# watchplb_mainboard_v1_0.net
KiCad netlist of a schematic drawn in EAGLE
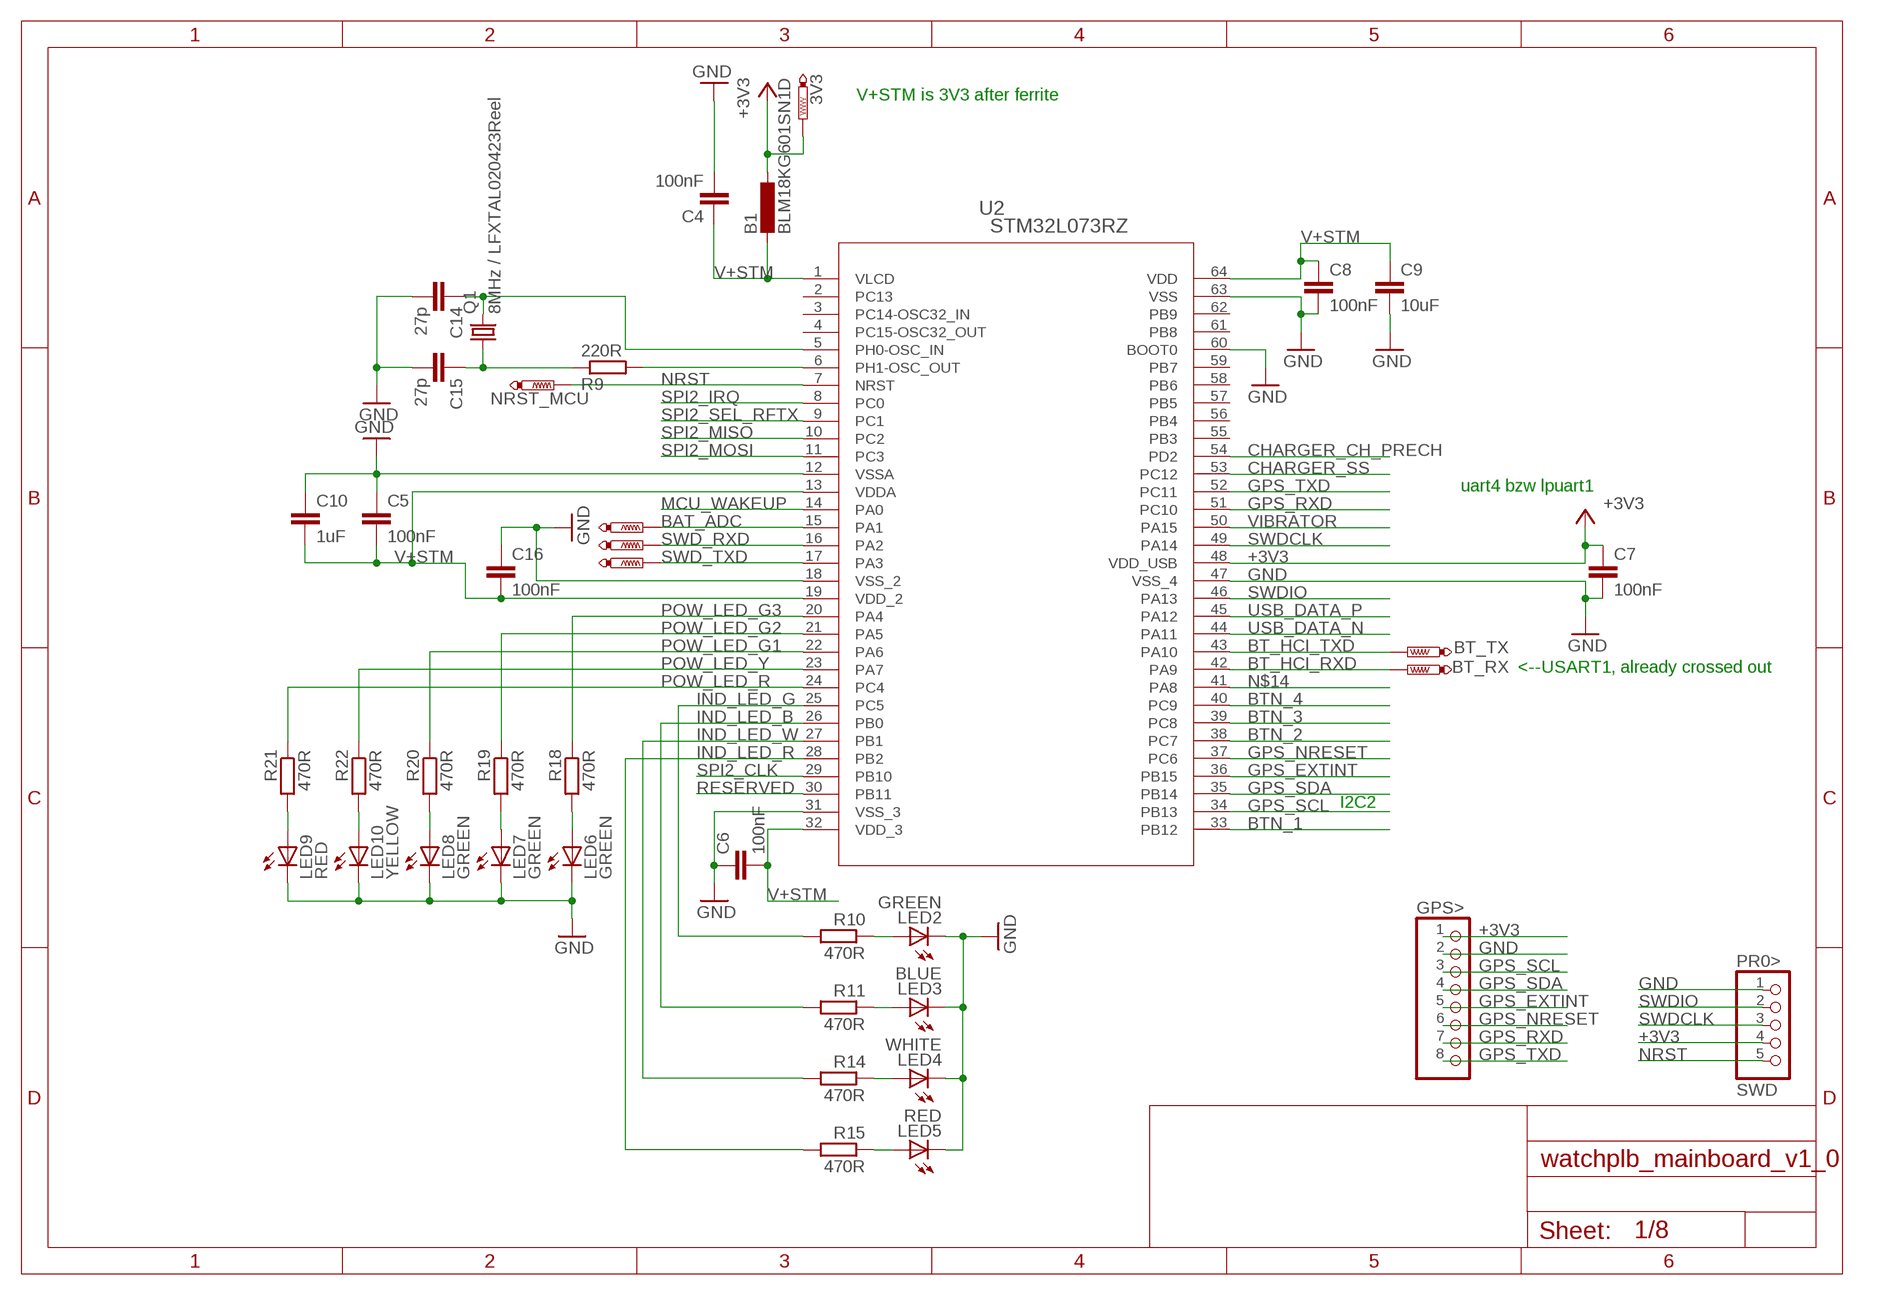
[diagram p0: schematic, sheet 1]
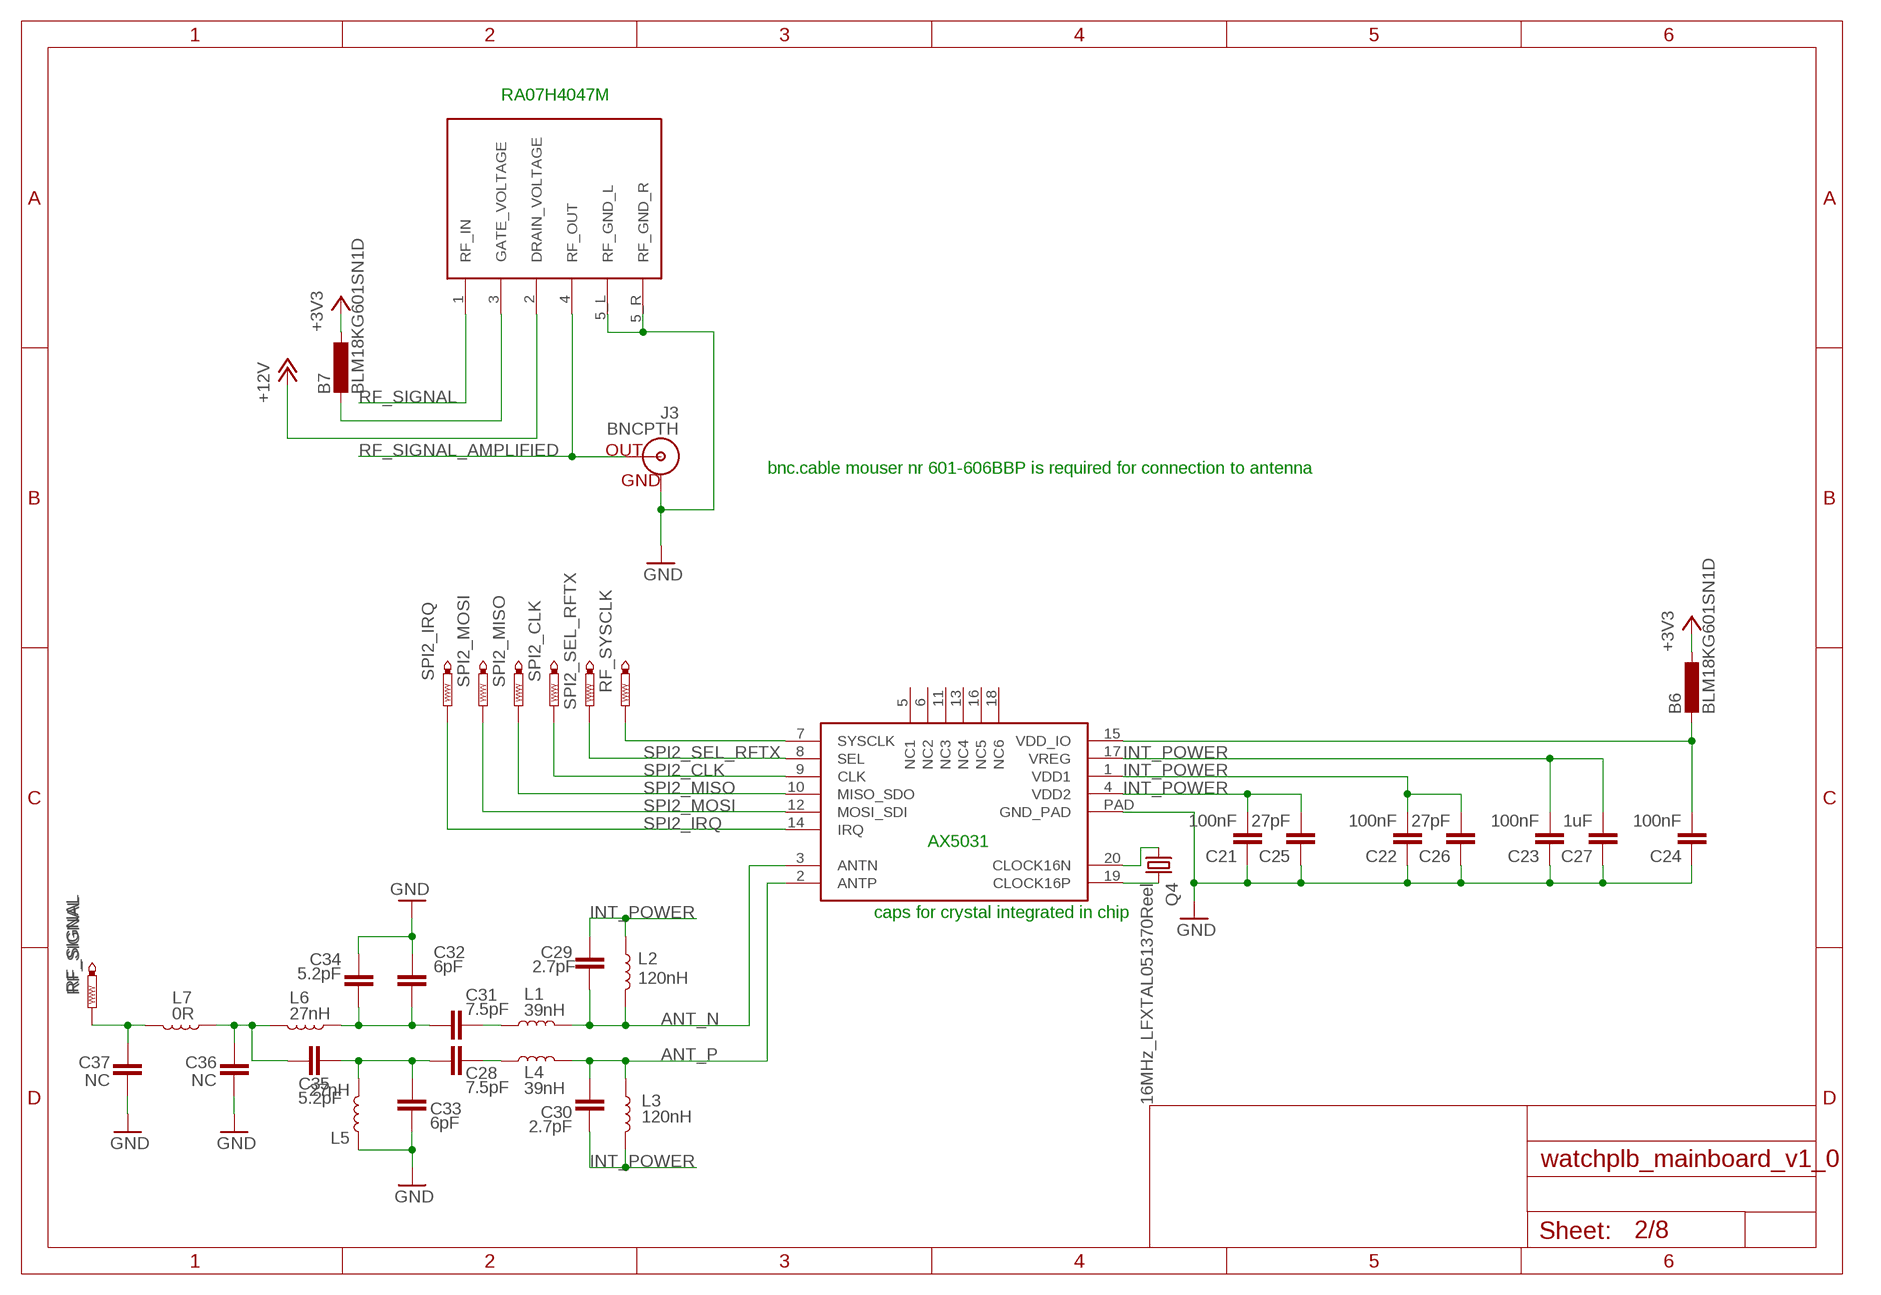
[diagram p1: schematic, sheet 2]
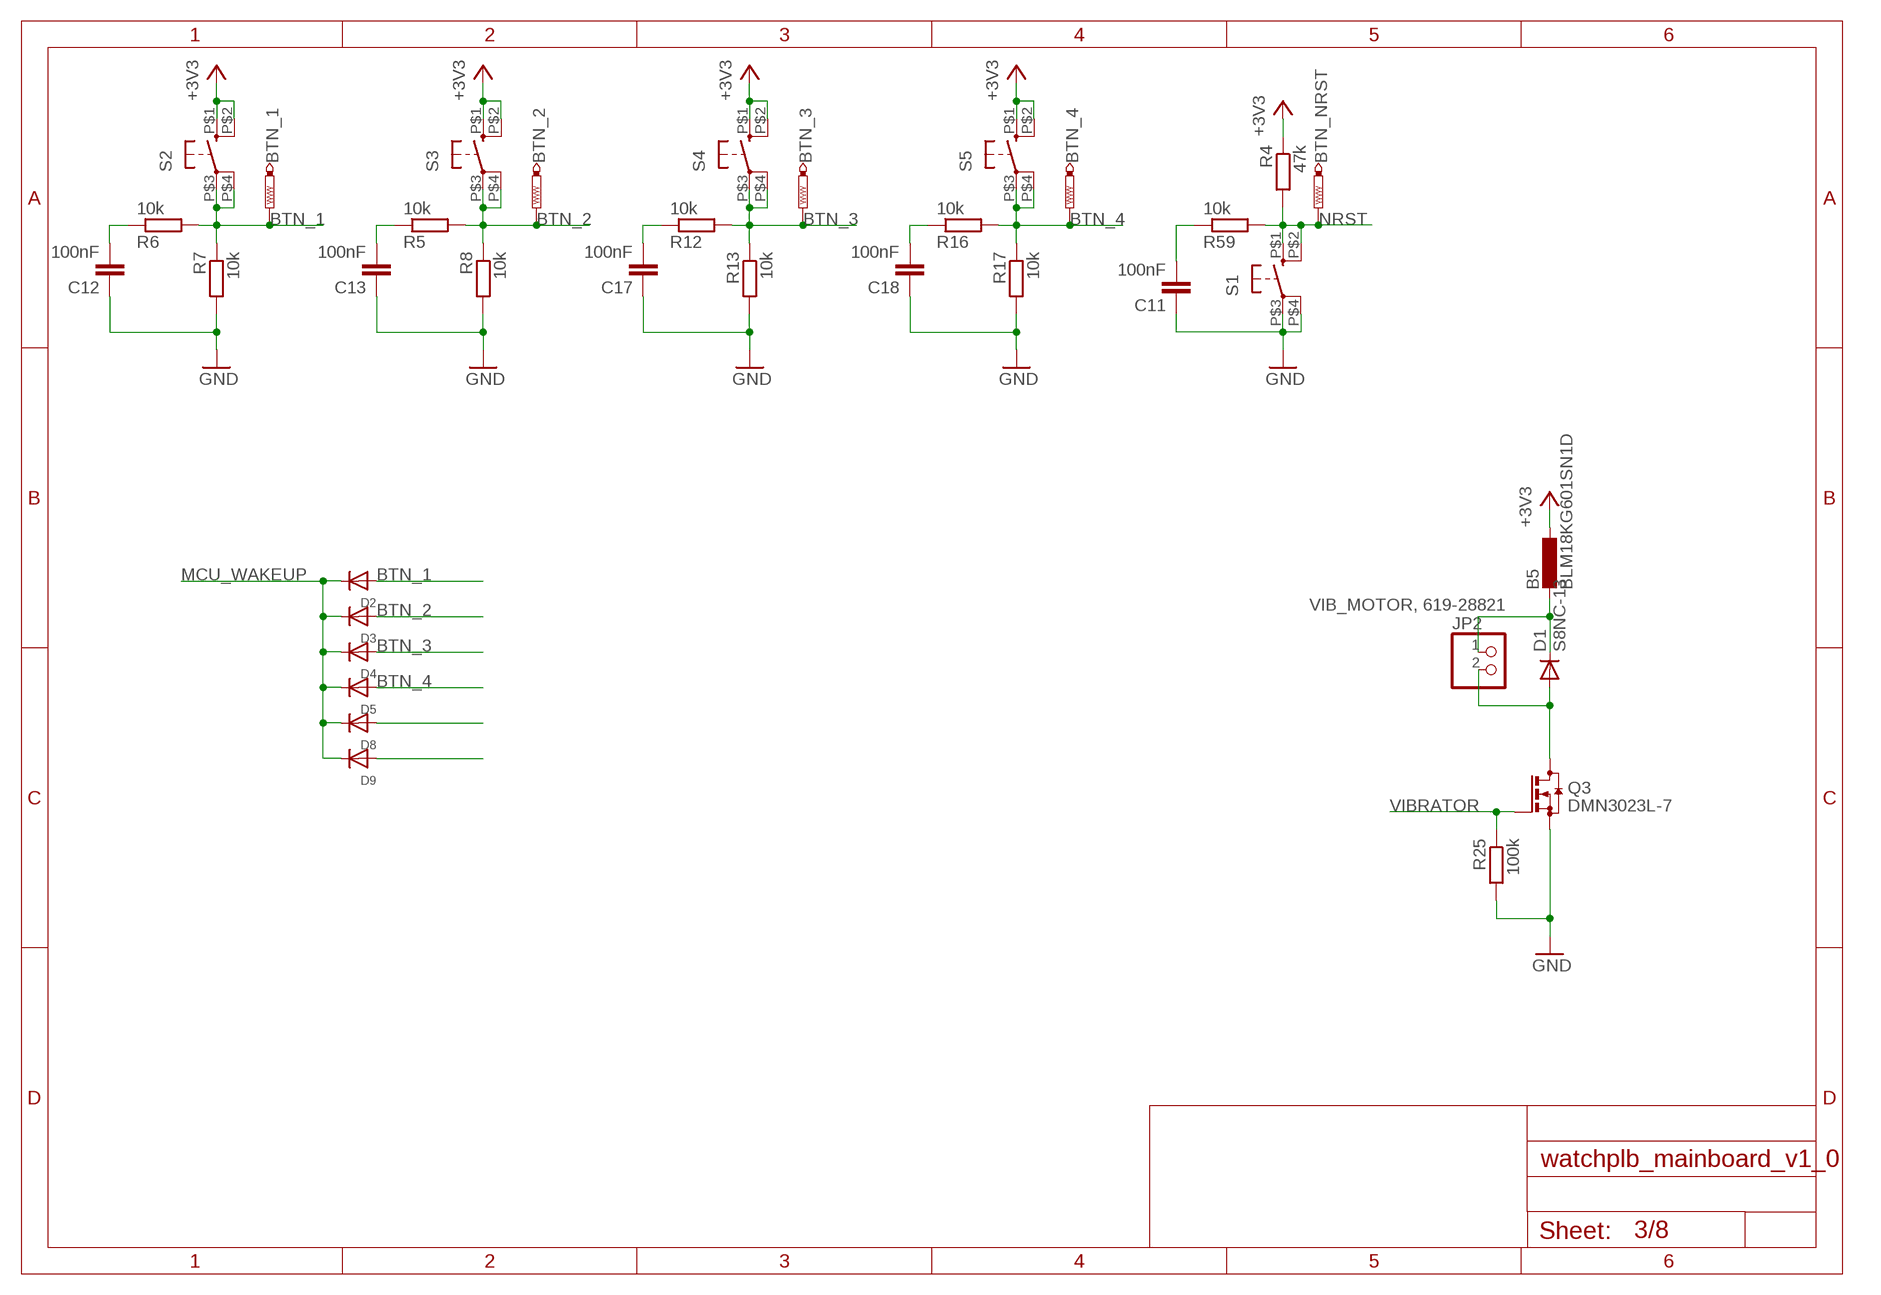
[diagram p2: schematic, sheet 3]
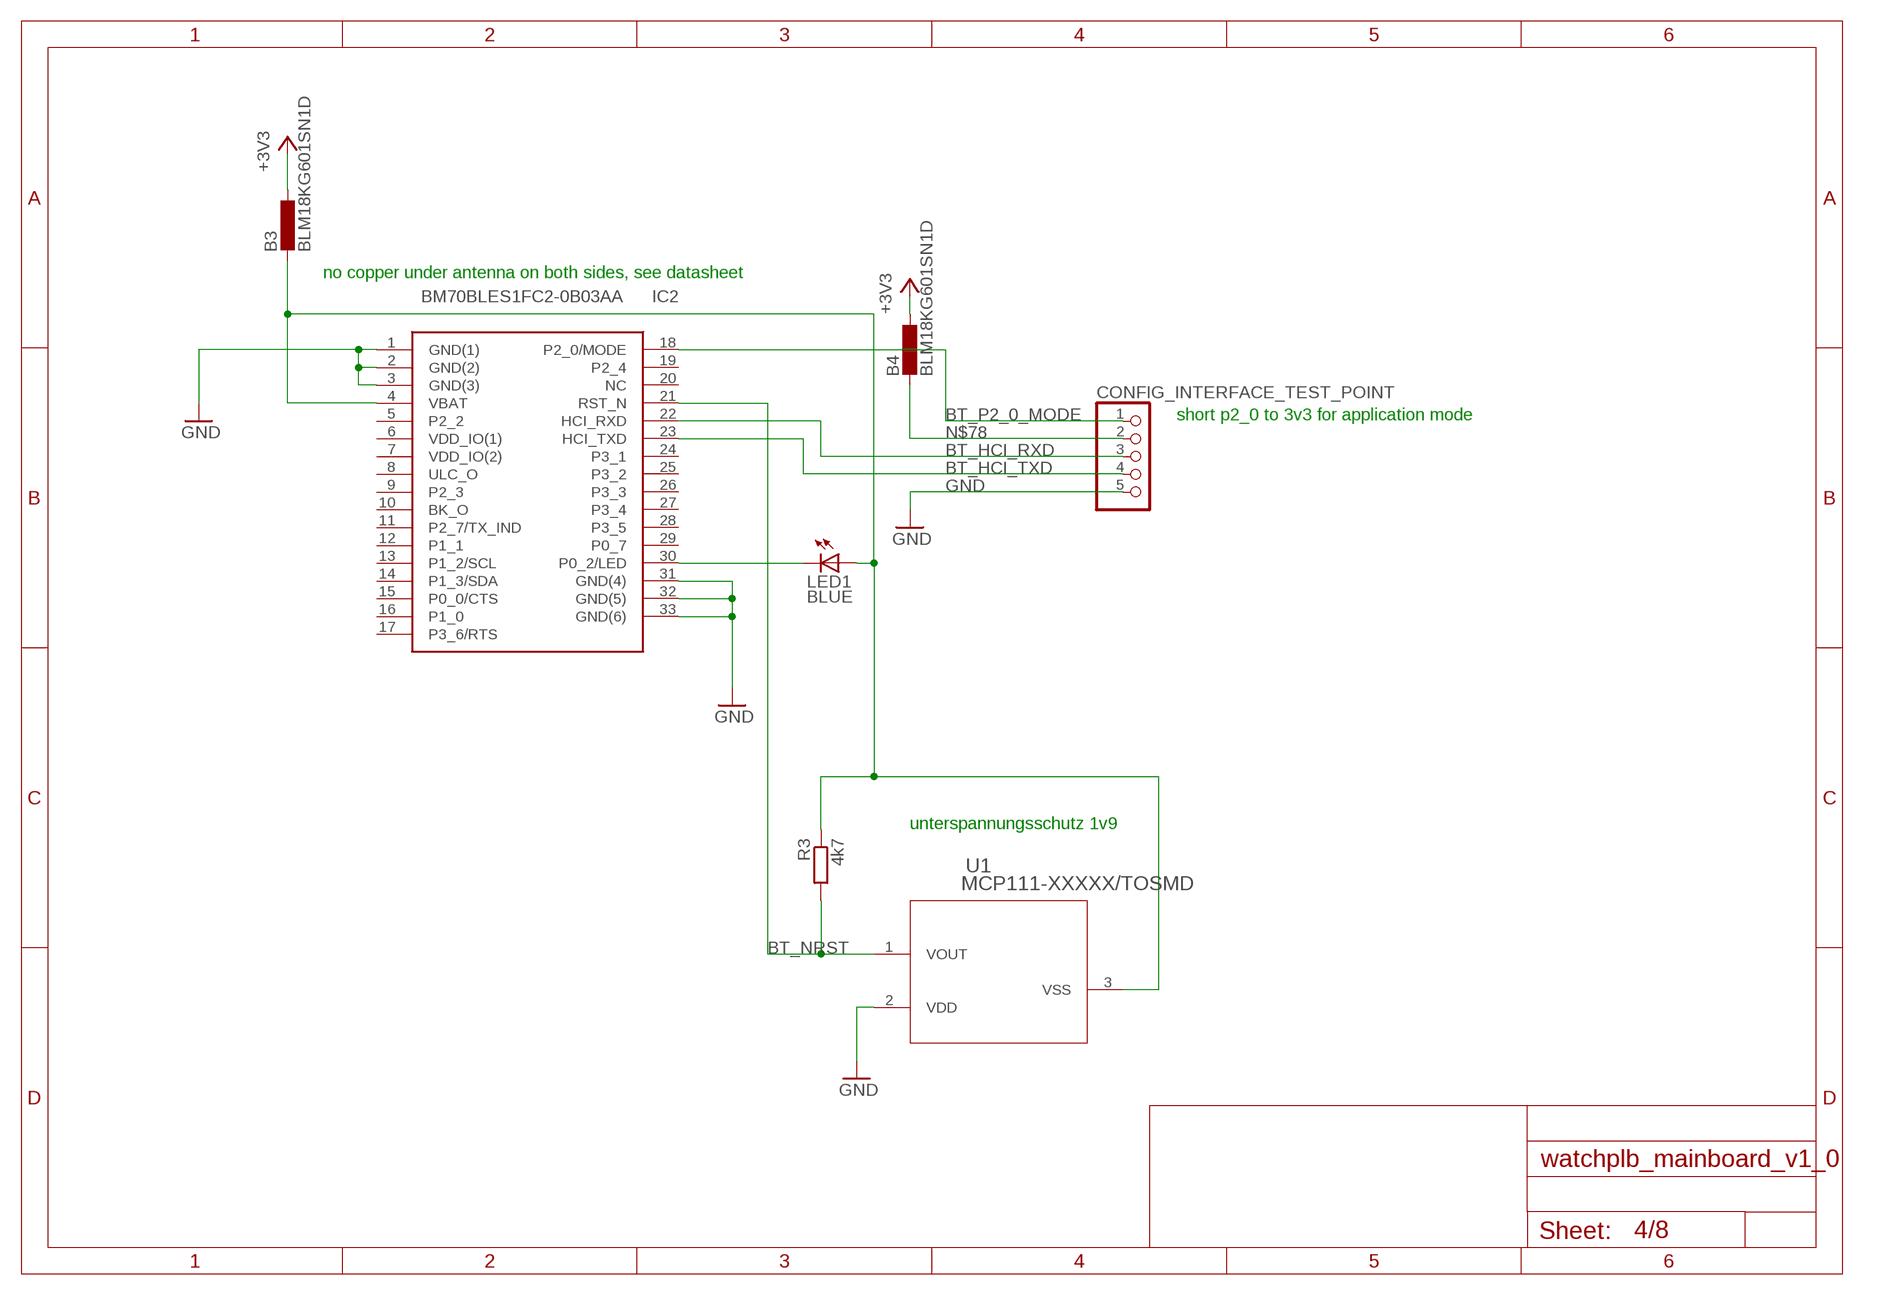
[diagram p3: schematic, sheet 4]
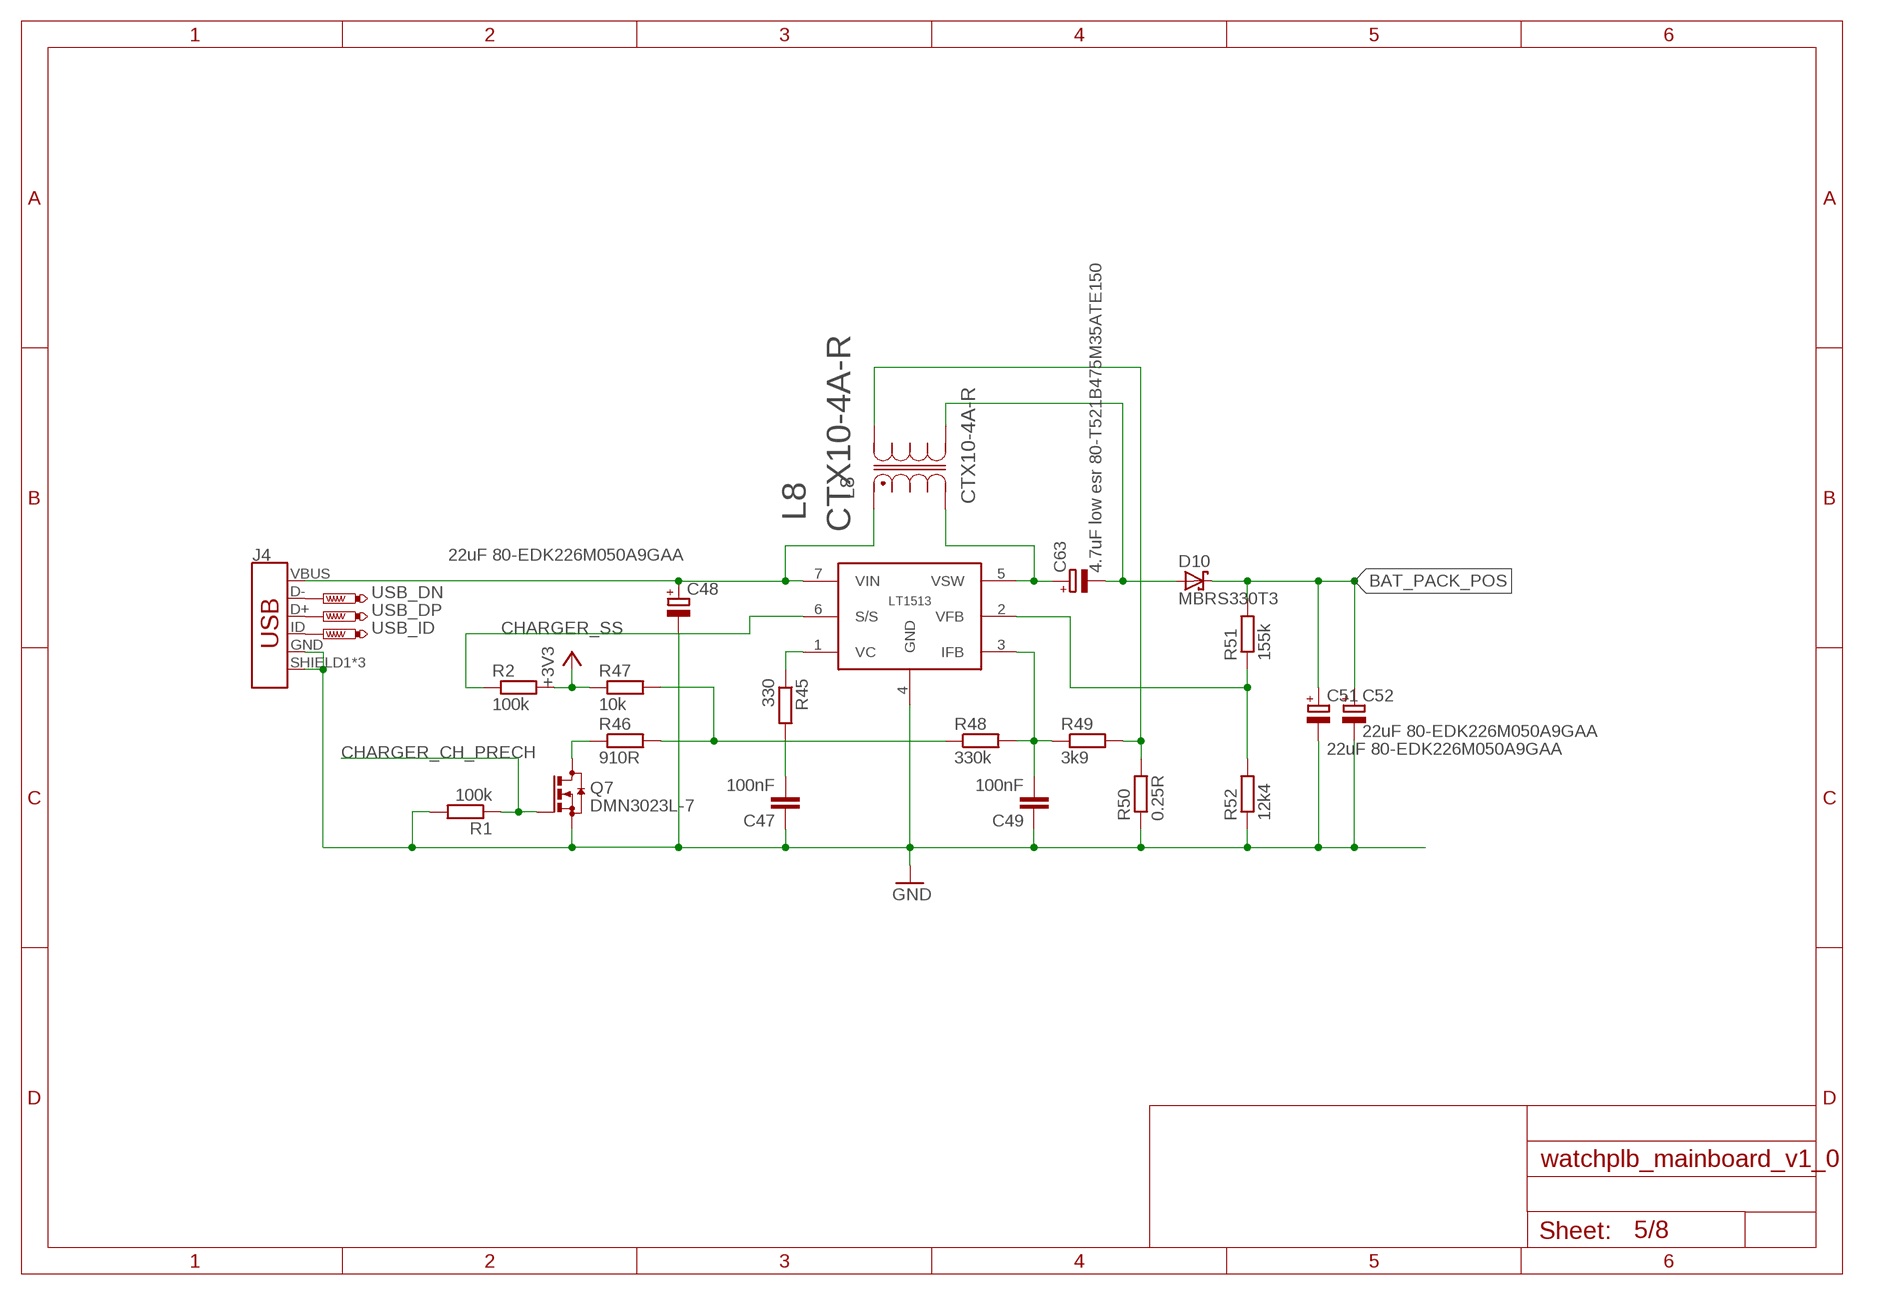
[diagram p4: schematic, sheet 5]
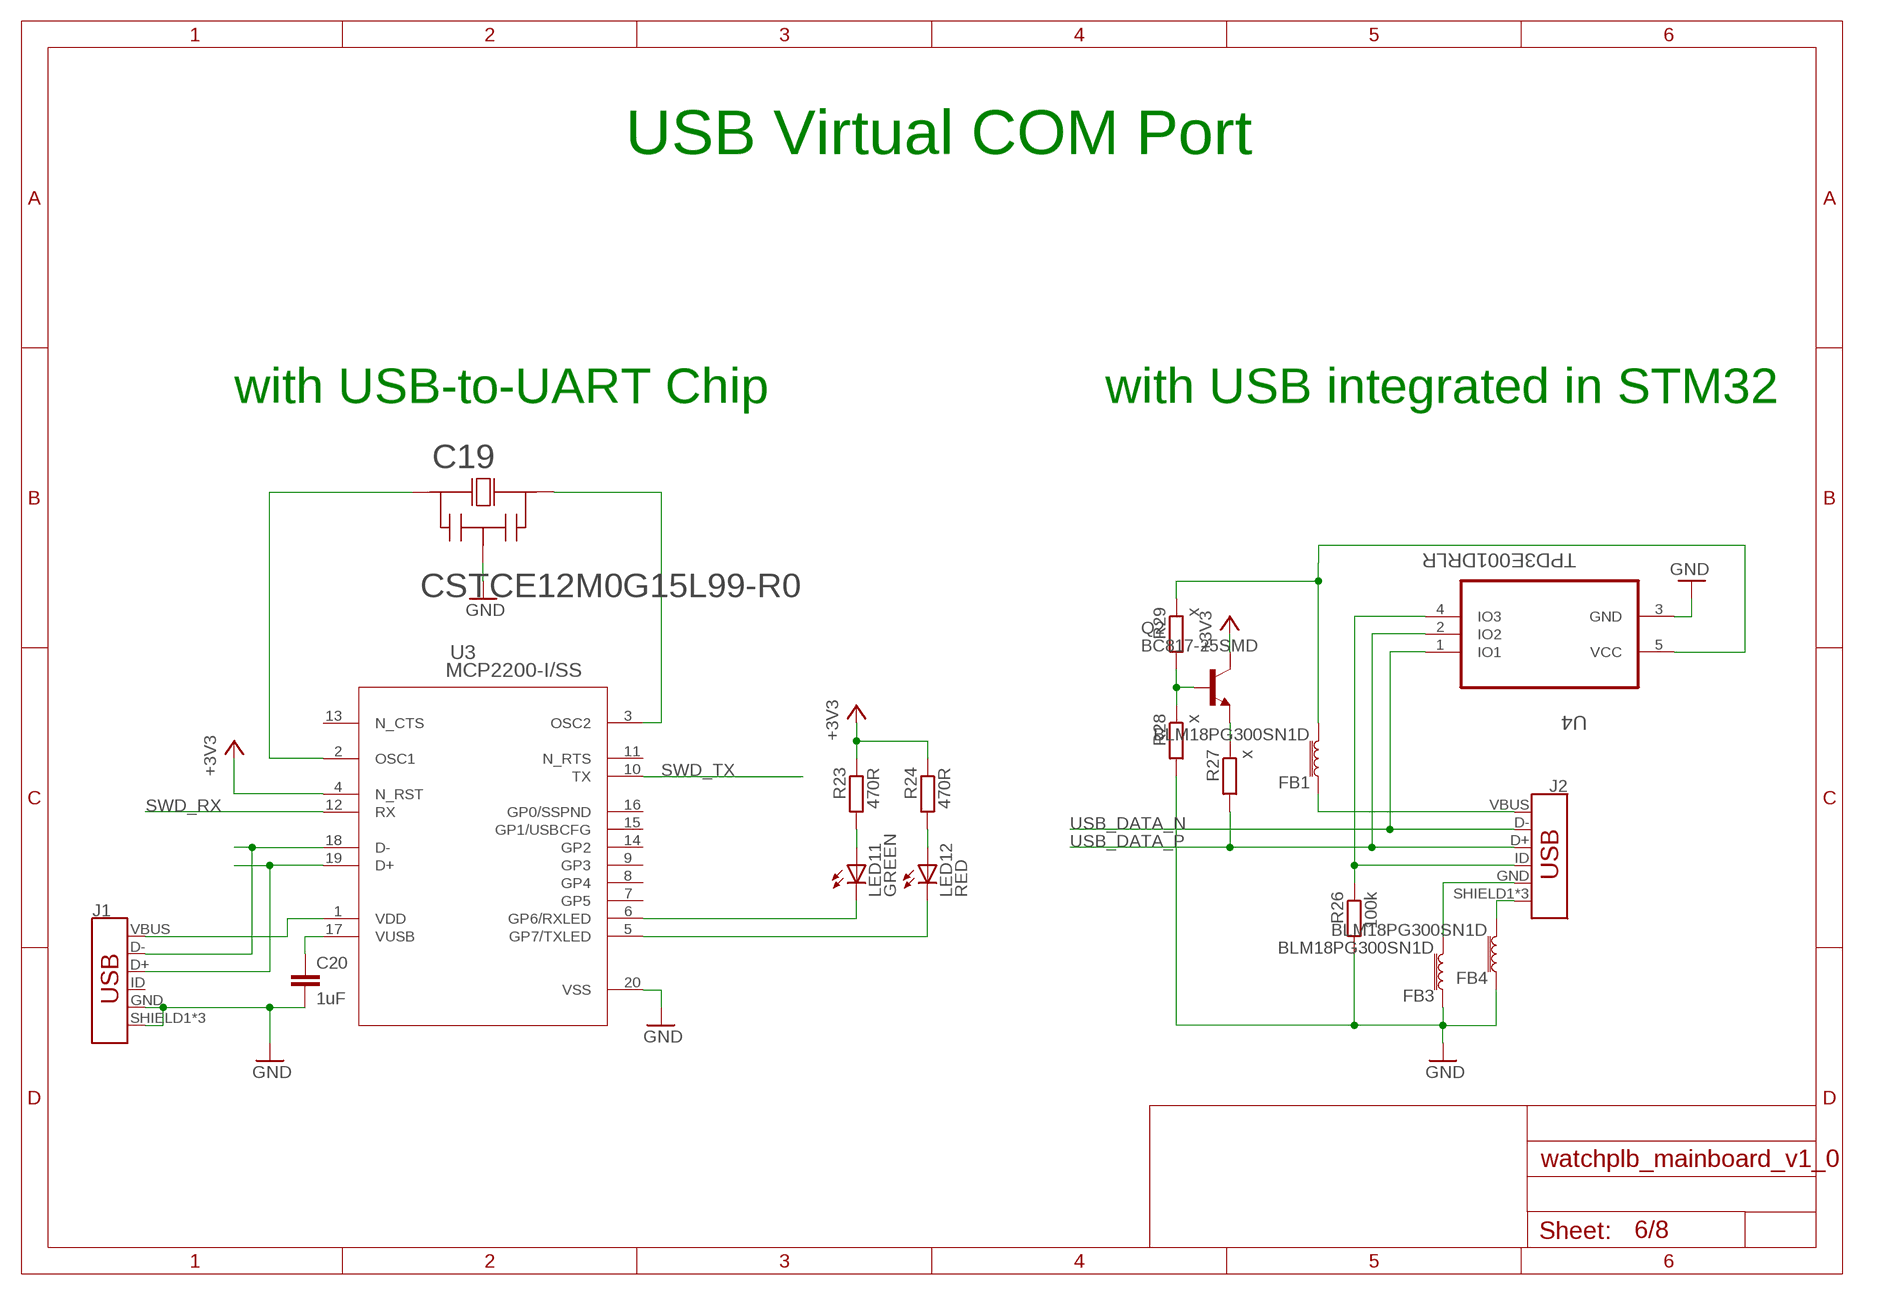
[diagram p5: schematic, sheet 6]
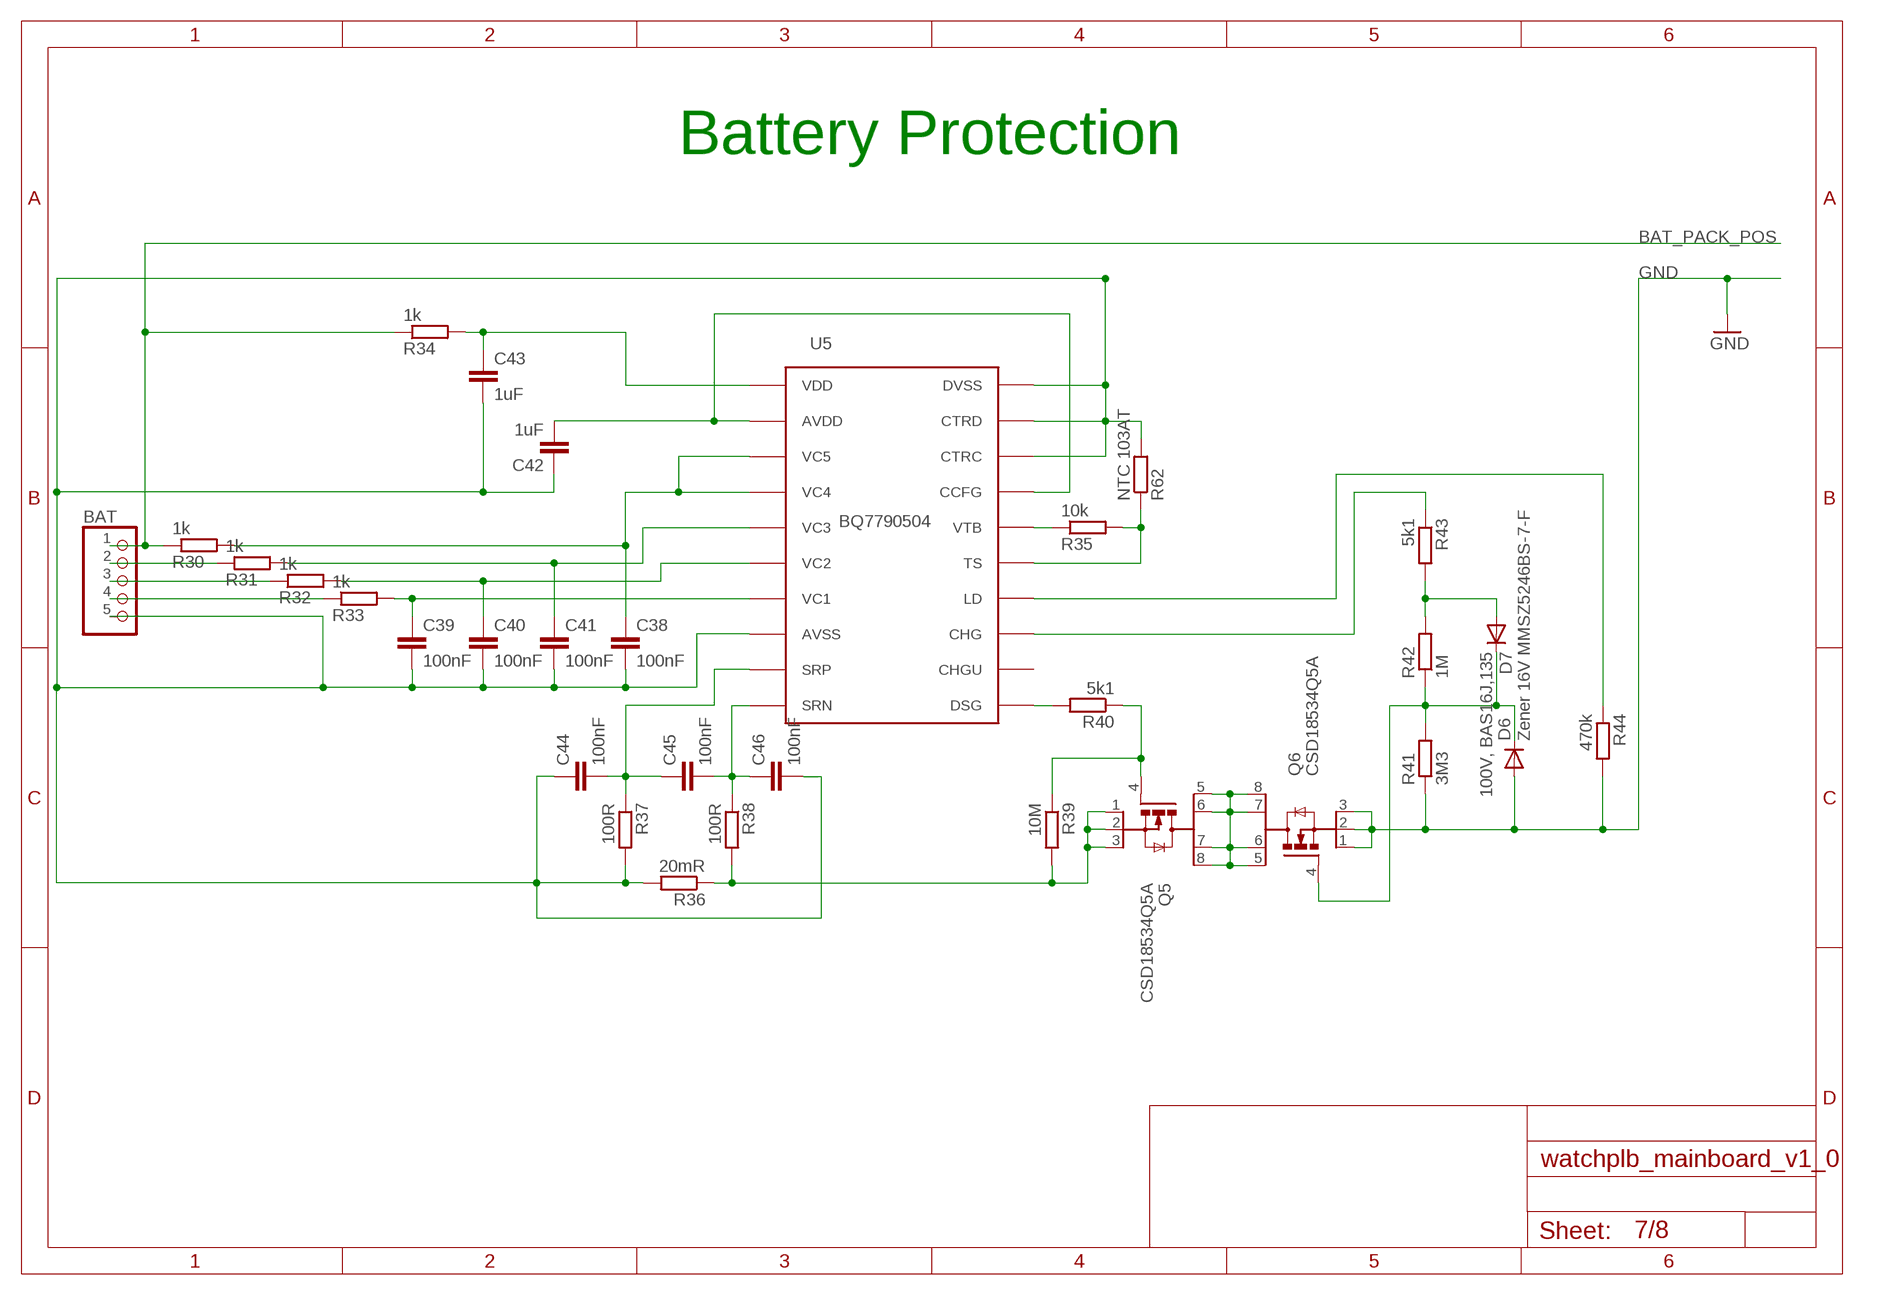
[diagram p6: schematic, sheet 7]
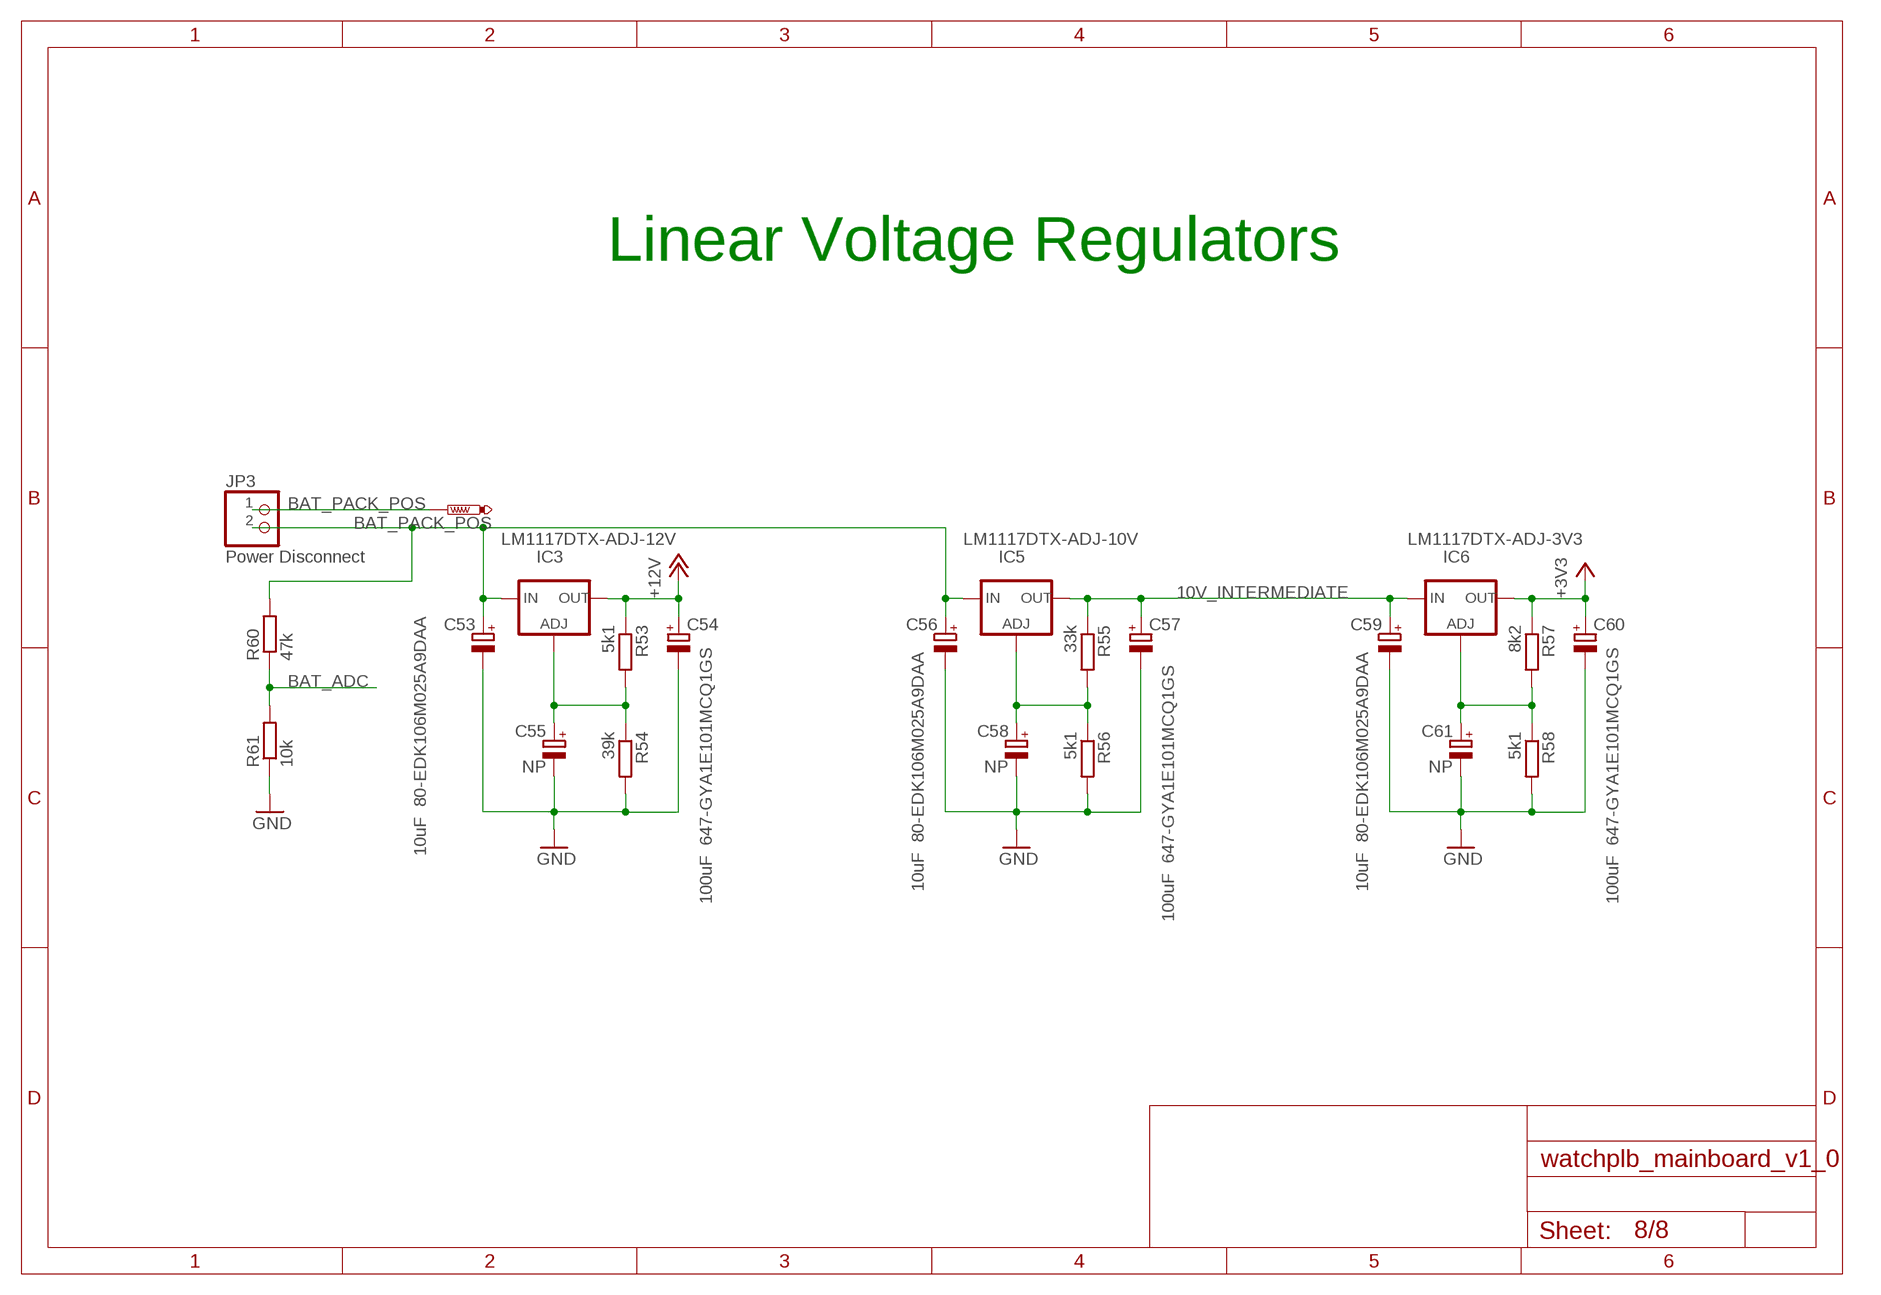
[diagram p7: schematic, sheet 8]

(export (version "E")
  (design (tool "Eeschema 10.0.6"))
  (components
    (comp (ref "C47")
      (value "100nF")
      (footprint "eagle-import:C0805K")
      (libsource (lib "eagle-import") (part "C-EUC0805K"))
    )
    (comp (ref "C48")
      (value "22uF 80-EDK226M050A9GAA")
      (footprint "eagle-import:PANASONIC_E")
      (libsource (lib "eagle-import") (part "CPOL-EUE"))
    )
    (comp (ref "C49")
      (value "100nF")
      (footprint "eagle-import:C0805K")
      (libsource (lib "eagle-import") (part "C-EUC0805K"))
    )
    (comp (ref "C51")
      (value "22uF 80-EDK226M050A9GAA")
      (footprint "eagle-import:PANASONIC_E")
      (libsource (lib "eagle-import") (part "CPOL-EUE"))
    )
    (comp (ref "C52")
      (value "22uF 80-EDK226M050A9GAA")
      (footprint "eagle-import:PANASONIC_E")
      (libsource (lib "eagle-import") (part "CPOL-EUE"))
    )
    (comp (ref "C63")
      (value "4.7uF low esr 80-T521B475M35ATE150")
      (footprint "eagle-import:B_3528-21R")
      (libsource (lib "eagle-import") (part "CPOL-EUB/3528-21R"))
    )
    (comp (ref "D10")
      (value "MBRS330T3")
      (footprint "eagle-import:SMC")
      (libsource (lib "eagle-import") (part "MBRS30T33"))
    )
    (comp (ref "IC1")
      (value "LT1513")
      (footprint "eagle-import:TO220-7")
      (libsource (lib "eagle-import") (part "LT1513"))
    )
    (comp (ref "J4")
      (value "USB_MICRO-B_FEMALE-SMT")
      (footprint "eagle-import:USB-B-MICRO-SMD")
      (libsource (lib "eagle-import") (part "USB_MICRO-B_FEMALE-SMT"))
    )
    (comp (ref "L8")
      (value "CTX10-4A-R")
      (footprint "eagle-import:INDM115115X635N")
      (fields (field (name "MF") "Eaton"))
      (libsource (lib "eagle-import") (part "CTX10-4A-R"))
    )
    (comp (ref "Q7")
      (value "DMN3023L-7")
      (footprint "eagle-import:SOT23")
      (libsource (lib "eagle-import") (part "BSS123"))
    )
    (comp (ref "R1")
      (value "100k")
      (footprint "eagle-import:M0805")
      (libsource (lib "eagle-import") (part "R-EU_M0805"))
    )
    (comp (ref "R2")
      (value "100k")
      (footprint "eagle-import:M0805")
      (libsource (lib "eagle-import") (part "R-EU_M0805"))
    )
    (comp (ref "R45")
      (value "330")
      (footprint "eagle-import:M0805")
      (libsource (lib "eagle-import") (part "R-EU_M0805"))
    )
    (comp (ref "R46")
      (value "910R")
      (footprint "eagle-import:M0805")
      (libsource (lib "eagle-import") (part "R-EU_M0805"))
    )
    (comp (ref "R47")
      (value "10k")
      (footprint "eagle-import:M0805")
      (libsource (lib "eagle-import") (part "R-EU_M0805"))
    )
    (comp (ref "R48")
      (value "330k")
      (footprint "eagle-import:M0805")
      (libsource (lib "eagle-import") (part "R-EU_M0805"))
    )
    (comp (ref "R49")
      (value "3k9")
      (footprint "eagle-import:M0805")
      (libsource (lib "eagle-import") (part "R-EU_M0805"))
    )
    (comp (ref "R50")
      (value "0.25R")
      (footprint "eagle-import:R2512")
      (libsource (lib "eagle-import") (part "R-EU_R2512"))
    )
    (comp (ref "R51")
      (value "155k")
      (footprint "eagle-import:M0805")
      (libsource (lib "eagle-import") (part "R-EU_M0805"))
    )
    (comp (ref "R52")
      (value "12k4")
      (footprint "eagle-import:M0805")
      (libsource (lib "eagle-import") (part "R-EU_M0805"))
    )
    (comp (ref "USB_DN")
      (value "PTR1B1,27")
      (footprint "eagle-import:B1,27")
      (libsource (lib "eagle-import") (part "PTR1B1,27"))
    )
    (comp (ref "USB_DP")
      (value "PTR1B1,27")
      (footprint "eagle-import:B1,27")
      (libsource (lib "eagle-import") (part "PTR1B1,27"))
    )
    (comp (ref "USB_ID")
      (value "PTR1B1,27")
      (footprint "eagle-import:B1,27")
      (libsource (lib "eagle-import") (part "PTR1B1,27"))
    )
    (comp (ref "B6")
      (value "BLM18KG601SN1D")
      (footprint "eagle-import:L0603")
      (libsource (lib "eagle-import") (part "B-EU_B0603"))
    )
    (comp (ref "B7")
      (value "BLM18KG601SN1D")
      (footprint "eagle-import:L0603")
      (libsource (lib "eagle-import") (part "B-EU_B0603"))
    )
    (comp (ref "C21")
      (value "100nF")
      (footprint "eagle-import:C0805")
      (libsource (lib "eagle-import") (part "C-EUC0805"))
    )
    (comp (ref "C22")
      (value "100nF")
      (footprint "eagle-import:C0805")
      (libsource (lib "eagle-import") (part "C-EUC0805"))
    )
    (comp (ref "C23")
      (value "100nF")
      (footprint "eagle-import:C0805")
      (libsource (lib "eagle-import") (part "C-EUC0805"))
    )
    (comp (ref "C24")
      (value "100nF")
      (footprint "eagle-import:C0805")
      (libsource (lib "eagle-import") (part "C-EUC0805"))
    )
    (comp (ref "C25")
      (value "27pF")
      (footprint "eagle-import:C0805")
      (libsource (lib "eagle-import") (part "C-EUC0805"))
    )
    (comp (ref "C26")
      (value "27pF")
      (footprint "eagle-import:C0805")
      (libsource (lib "eagle-import") (part "C-EUC0805"))
    )
    (comp (ref "C27")
      (value "1uF")
      (footprint "eagle-import:C0805")
      (libsource (lib "eagle-import") (part "C-EUC0805"))
    )
    (comp (ref "C28")
      (value "7.5pF")
      (footprint "eagle-import:C0805")
      (libsource (lib "eagle-import") (part "C-EUC0805"))
    )
    (comp (ref "C29")
      (value "2.7pF")
      (footprint "eagle-import:C0805")
      (libsource (lib "eagle-import") (part "C-EUC0805"))
    )
    (comp (ref "C30")
      (value "2.7pF")
      (footprint "eagle-import:C0805")
      (libsource (lib "eagle-import") (part "C-EUC0805"))
    )
    (comp (ref "C31")
      (value "7.5pF")
      (footprint "eagle-import:C0805")
      (libsource (lib "eagle-import") (part "C-EUC0805"))
    )
    (comp (ref "C32")
      (value "6pF")
      (footprint "eagle-import:C0805")
      (libsource (lib "eagle-import") (part "C-EUC0805"))
    )
    (comp (ref "C33")
      (value "6pF")
      (footprint "eagle-import:C0805")
      (libsource (lib "eagle-import") (part "C-EUC0805"))
    )
    (comp (ref "C34")
      (value "5.2pF")
      (footprint "eagle-import:C0805")
      (libsource (lib "eagle-import") (part "C-EUC0805"))
    )
    (comp (ref "C35")
      (value "5.2pF")
      (footprint "eagle-import:C0805")
      (libsource (lib "eagle-import") (part "C-EUC0805"))
    )
    (comp (ref "C36")
      (value "NC")
      (footprint "eagle-import:C0805")
      (libsource (lib "eagle-import") (part "C-EUC0805"))
    )
    (comp (ref "C37")
      (value "NC")
      (footprint "eagle-import:C0805")
      (libsource (lib "eagle-import") (part "C-EUC0805"))
    )
    (comp (ref "IC4")
      (value "AX5031")
      (footprint "eagle-import:QFN20")
      (libsource (lib "eagle-import") (part "AX5031"))
    )
    (comp (ref "J3")
      (value "BNCPTH")
      (footprint "eagle-import:BNC")
      (libsource (lib "eagle-import") (part "BNCPTH"))
    )
    (comp (ref "L1")
      (value "39nH")
      (footprint "eagle-import:0805")
      (libsource (lib "eagle-import") (part "INDUCTOR-0805-3.3UH"))
    )
    (comp (ref "L2")
      (value "120nH")
      (footprint "eagle-import:0805")
      (libsource (lib "eagle-import") (part "INDUCTOR-0805-3.3UH"))
    )
    (comp (ref "L3")
      (value "120nH")
      (footprint "eagle-import:0805")
      (libsource (lib "eagle-import") (part "INDUCTOR-0805-3.3UH"))
    )
    (comp (ref "L4")
      (value "39nH")
      (footprint "eagle-import:0805")
      (libsource (lib "eagle-import") (part "INDUCTOR-0805-3.3UH"))
    )
    (comp (ref "L5")
      (value "27nH")
      (footprint "eagle-import:0805")
      (libsource (lib "eagle-import") (part "INDUCTOR-0805-3.3UH"))
    )
    (comp (ref "L6")
      (value "27nH")
      (footprint "eagle-import:0805")
      (libsource (lib "eagle-import") (part "INDUCTOR-0805-3.3UH"))
    )
    (comp (ref "L7")
      (value "0R")
      (footprint "eagle-import:0805")
      (libsource (lib "eagle-import") (part "INDUCTOR-0805-3.3UH"))
    )
    (comp (ref "Q4")
      (value "16MHz_LFXTAL051370Reel")
      (footprint "eagle-import:HC49UP")
      (libsource (lib "eagle-import") (part "CRYSTALHC49UP"))
    )
    (comp (ref "RF_SIGNAL")
      (value "PTR1B2,54")
      (footprint "eagle-import:B2,54")
      (libsource (lib "eagle-import") (part "PTR1B2,54"))
    )
    (comp (ref "RF_SYSCLK")
      (value "PTR1B1,27")
      (footprint "eagle-import:B1,27")
      (libsource (lib "eagle-import") (part "PTR1B1,27"))
    )
    (comp (ref "SPI2_CLK")
      (value "PTR1B1,27")
      (footprint "eagle-import:B1,27")
      (libsource (lib "eagle-import") (part "PTR1B1,27"))
    )
    (comp (ref "SPI2_IRQ")
      (value "PTR1B1,27")
      (footprint "eagle-import:B1,27")
      (libsource (lib "eagle-import") (part "PTR1B1,27"))
    )
    (comp (ref "SPI2_MISO")
      (value "PTR1B1,27")
      (footprint "eagle-import:B1,27")
      (libsource (lib "eagle-import") (part "PTR1B1,27"))
    )
    (comp (ref "SPI2_MOSI")
      (value "PTR1B1,27")
      (footprint "eagle-import:B1,27")
      (libsource (lib "eagle-import") (part "PTR1B1,27"))
    )
    (comp (ref "SPI2_SEL_RFTX")
      (value "PTR1B1,27")
      (footprint "eagle-import:B1,27")
      (libsource (lib "eagle-import") (part "PTR1B1,27"))
    )
    (comp (ref "U$2")
      (value "RA07H4047M")
      (footprint "eagle-import:RA07H4047M")
      (libsource (lib "eagle-import") (part "RA07H4047M"))
    )
    (comp (ref "C19")
      (value "CSTCE12M0G15L99-R0")
      (footprint "eagle-import:CSTCE")
      (fields (field (name "MANUFACTURER_PART_NUMBER") "CSTCE8M00G52R0"))
      (libsource (lib "eagle-import") (part "CSTCE8M00G52-R0"))
    )
    (comp (ref "C20")
      (value "1uF")
      (footprint "eagle-import:C0805")
      (libsource (lib "eagle-import") (part "C-EUC0805"))
    )
    (comp (ref "FB1")
      (value "BLM18PG300SN1D")
      (footprint "eagle-import:0603")
      (libsource (lib "eagle-import") (part "FERRITE_BEAD-0603"))
    )
    (comp (ref "FB3")
      (value "BLM18PG300SN1D")
      (footprint "eagle-import:0603")
      (libsource (lib "eagle-import") (part "FERRITE_BEAD-0603"))
    )
    (comp (ref "FB4")
      (value "BLM18PG300SN1D")
      (footprint "eagle-import:0603")
      (libsource (lib "eagle-import") (part "FERRITE_BEAD-0603"))
    )
    (comp (ref "J1")
      (value "USB_MICRO-B_FEMALE-SMT")
      (footprint "eagle-import:USB-B-MICRO-SMD")
      (libsource (lib "eagle-import") (part "USB_MICRO-B_FEMALE-SMT"))
    )
    (comp (ref "J2")
      (value "USB_MICRO-B_FEMALE-SMT")
      (footprint "eagle-import:USB-B-MICRO-SMD")
      (libsource (lib "eagle-import") (part "USB_MICRO-B_FEMALE-SMT"))
    )
    (comp (ref "LED11")
      (value "GREEN")
      (footprint "eagle-import:CHIP-LED0805")
      (libsource (lib "eagle-import") (part "LEDCHIP-LED0805"))
    )
    (comp (ref "LED12")
      (value "RED")
      (footprint "eagle-import:CHIP-LED0805")
      (libsource (lib "eagle-import") (part "LEDCHIP-LED0805"))
    )
    (comp (ref "Q2")
      (value "BC817-25SMD")
      (footprint "eagle-import:SOT23-BEC")
      (libsource (lib "eagle-import") (part "BC817SMD-25"))
    )
    (comp (ref "R23")
      (value "470R")
      (footprint "eagle-import:M0805")
      (libsource (lib "eagle-import") (part "R-EU_M0805"))
    )
    (comp (ref "R24")
      (value "470R")
      (footprint "eagle-import:M0805")
      (libsource (lib "eagle-import") (part "R-EU_M0805"))
    )
    (comp (ref "R26")
      (value "100k")
      (footprint "eagle-import:M0805")
      (libsource (lib "eagle-import") (part "R-EU_M0805"))
    )
    (comp (ref "R27")
      (value "x")
      (footprint "eagle-import:M0805")
      (libsource (lib "eagle-import") (part "R-EU_M0805"))
    )
    (comp (ref "R28")
      (value "x")
      (footprint "eagle-import:M0805")
      (libsource (lib "eagle-import") (part "R-EU_M0805"))
    )
    (comp (ref "R29")
      (value "x")
      (footprint "eagle-import:M0805")
      (libsource (lib "eagle-import") (part "R-EU_M0805"))
    )
    (comp (ref "U3")
      (value "MCP2200-I/SS")
      (footprint "eagle-import:SSOP20_MC")
      (fields (field (name "MANUFACTURER_PART_NUMBER") "mcp2200iss"))
      (libsource (lib "eagle-import") (part "MCP2200-I/SS"))
    )
    (comp (ref "U4")
      (value "TPD3E001DRLR")
      (footprint "eagle-import:SOT50P160X60-5N")
      (libsource (lib "eagle-import") (part "TPD3E001DRLR"))
    )
    (comp (ref "B3")
      (value "BLM18KG601SN1D")
      (footprint "eagle-import:L0603")
      (libsource (lib "eagle-import") (part "B-EU_B0603"))
    )
    (comp (ref "B4")
      (value "BLM18KG601SN1D")
      (footprint "eagle-import:L0603")
      (libsource (lib "eagle-import") (part "B-EU_B0603"))
    )
    (comp (ref "CONFIG_INTERFACE_TEST_POINT")
      (value "PINHD-1X5")
      (footprint "eagle-import:1X05")
      (libsource (lib "eagle-import") (part "PINHD-1X5"))
    )
    (comp (ref "IC2")
      (value "BM70BLES1FC2-0B03AA")
      (footprint "eagle-import:BM78SPPS5NC2_1")
      (libsource (lib "eagle-import") (part "BM70BLES1FC2-0B03AA"))
    )
    (comp (ref "LED1")
      (value "BLUE")
      (footprint "eagle-import:CHIP-LED0805")
      (libsource (lib "eagle-import") (part "LEDCHIP-LED0805"))
    )
    (comp (ref "R3")
      (value "4k7")
      (footprint "eagle-import:M0805")
      (libsource (lib "eagle-import") (part "R-EU_M0805"))
    )
    (comp (ref "U1")
      (value "MCP111-XXXXX/TOSMD")
      (footprint "eagle-import:SC70-3-R")
      (libsource (lib "eagle-import") (part "MCP111-XXXXX/TOSMD"))
    )
    (comp (ref "BAT_PACK_POS")
      (value "PTR1B1,27")
      (footprint "eagle-import:B1,27")
      (libsource (lib "eagle-import") (part "PTR1B1,27"))
    )
    (comp (ref "C53")
      (value "10uF 80-EDK106M025A9DAA")
      (footprint "eagle-import:PANASONIC_E")
      (libsource (lib "eagle-import") (part "CPOL-EUE"))
    )
    (comp (ref "C54")
      (value "100uF 647-GYA1E101MCQ1GS")
      (footprint "eagle-import:PANASONIC_E")
      (libsource (lib "eagle-import") (part "CPOL-EUE"))
    )
    (comp (ref "C55")
      (value "NP")
      (footprint "eagle-import:PANASONIC_E")
      (libsource (lib "eagle-import") (part "CPOL-EUE"))
    )
    (comp (ref "C56")
      (value "10uF 80-EDK106M025A9DAA")
      (footprint "eagle-import:PANASONIC_E")
      (libsource (lib "eagle-import") (part "CPOL-EUE"))
    )
    (comp (ref "C57")
      (value "100uF 647-GYA1E101MCQ1GS")
      (footprint "eagle-import:PANASONIC_E")
      (libsource (lib "eagle-import") (part "CPOL-EUE"))
    )
    (comp (ref "C58")
      (value "NP")
      (footprint "eagle-import:PANASONIC_E")
      (libsource (lib "eagle-import") (part "CPOL-EUE"))
    )
    (comp (ref "C59")
      (value "10uF 80-EDK106M025A9DAA")
      (footprint "eagle-import:PANASONIC_E")
      (libsource (lib "eagle-import") (part "CPOL-EUE"))
    )
    (comp (ref "C60")
      (value "100uF 647-GYA1E101MCQ1GS")
      (footprint "eagle-import:PANASONIC_E")
      (libsource (lib "eagle-import") (part "CPOL-EUE"))
    )
    (comp (ref "C61")
      (value "NP")
      (footprint "eagle-import:PANASONIC_E")
      (libsource (lib "eagle-import") (part "CPOL-EUE"))
    )
    (comp (ref "IC3")
      (value "LM1117DTX-ADJ-12V")
      (footprint "eagle-import:TO252")
      (libsource (lib "eagle-import") (part "LM1117DTX-ADJ"))
    )
    (comp (ref "IC5")
      (value "LM1117DTX-ADJ-10V")
      (footprint "eagle-import:TO252")
      (libsource (lib "eagle-import") (part "LM1117DTX-ADJ"))
    )
    (comp (ref "IC6")
      (value "LM1117DTX-ADJ-3V3")
      (footprint "eagle-import:TO252")
      (libsource (lib "eagle-import") (part "LM1117DTX-ADJ"))
    )
    (comp (ref "JP3")
      (value "Power Disconnect")
      (footprint "eagle-import:1X02")
      (libsource (lib "eagle-import") (part "PINHD-1X2"))
    )
    (comp (ref "R53")
      (value "5k1")
      (footprint "eagle-import:M0805")
      (libsource (lib "eagle-import") (part "R-EU_M0805"))
    )
    (comp (ref "R54")
      (value "39k")
      (footprint "eagle-import:M0805")
      (libsource (lib "eagle-import") (part "R-EU_M0805"))
    )
    (comp (ref "R55")
      (value "33k")
      (footprint "eagle-import:M0805")
      (libsource (lib "eagle-import") (part "R-EU_M0805"))
    )
    (comp (ref "R56")
      (value "5k1")
      (footprint "eagle-import:M0805")
      (libsource (lib "eagle-import") (part "R-EU_M0805"))
    )
    (comp (ref "R57")
      (value "8k2")
      (footprint "eagle-import:M0805")
      (libsource (lib "eagle-import") (part "R-EU_M0805"))
    )
    (comp (ref "R58")
      (value "5k1")
      (footprint "eagle-import:M0805")
      (libsource (lib "eagle-import") (part "R-EU_M0805"))
    )
    (comp (ref "R60")
      (value "47k")
      (footprint "eagle-import:M0805")
      (libsource (lib "eagle-import") (part "R-EU_M0805"))
    )
    (comp (ref "R61")
      (value "10k")
      (footprint "eagle-import:M0805")
      (libsource (lib "eagle-import") (part "R-EU_M0805"))
    )
    (comp (ref "B5")
      (value "BLM18KG601SN1D")
      (footprint "eagle-import:L0603")
      (libsource (lib "eagle-import") (part "B-EU_B0603"))
    )
    (comp (ref "BTN_1")
      (value "PTR1B1,27")
      (footprint "eagle-import:B1,27")
      (libsource (lib "eagle-import") (part "PTR1B1,27"))
    )
    (comp (ref "BTN_2")
      (value "PTR1B1,27")
      (footprint "eagle-import:B1,27")
      (libsource (lib "eagle-import") (part "PTR1B1,27"))
    )
    (comp (ref "BTN_3")
      (value "PTR1B1,27")
      (footprint "eagle-import:B1,27")
      (libsource (lib "eagle-import") (part "PTR1B1,27"))
    )
    (comp (ref "BTN_4")
      (value "PTR1B1,27")
      (footprint "eagle-import:B1,27")
      (libsource (lib "eagle-import") (part "PTR1B1,27"))
    )
    (comp (ref "BTN_NRST")
      (value "PTR1B1,27")
      (footprint "eagle-import:B1,27")
      (libsource (lib "eagle-import") (part "PTR1B1,27"))
    )
    (comp (ref "C11")
      (value "100nF")
      (footprint "eagle-import:C0805")
      (libsource (lib "eagle-import") (part "C-EUC0805"))
    )
    (comp (ref "C12")
      (value "100nF")
      (footprint "eagle-import:C0805")
      (libsource (lib "eagle-import") (part "C-EUC0805"))
    )
    (comp (ref "C13")
      (value "100nF")
      (footprint "eagle-import:C0805")
      (libsource (lib "eagle-import") (part "C-EUC0805"))
    )
    (comp (ref "C17")
      (value "100nF")
      (footprint "eagle-import:C0805")
      (libsource (lib "eagle-import") (part "C-EUC0805"))
    )
    (comp (ref "C18")
      (value "100nF")
      (footprint "eagle-import:C0805")
      (libsource (lib "eagle-import") (part "C-EUC0805"))
    )
    (comp (ref "D1")
      (value "S8NC-13")
      (footprint "eagle-import:SMC")
      (libsource (lib "eagle-import") (part "DIODE-SMC"))
    )
    (comp (ref "D2")
      (value "DIODESOD-123")
      (footprint "eagle-import:SOD-123")
      (libsource (lib "eagle-import") (part "DIODESOD-123"))
    )
    (comp (ref "D3")
      (value "DIODESOD-123")
      (footprint "eagle-import:SOD-123")
      (libsource (lib "eagle-import") (part "DIODESOD-123"))
    )
    (comp (ref "D4")
      (value "DIODESOD-123")
      (footprint "eagle-import:SOD-123")
      (libsource (lib "eagle-import") (part "DIODESOD-123"))
    )
    (comp (ref "D5")
      (value "DIODESOD-123")
      (footprint "eagle-import:SOD-123")
      (libsource (lib "eagle-import") (part "DIODESOD-123"))
    )
    (comp (ref "D8")
      (value "DIODESOD-123")
      (footprint "eagle-import:SOD-123")
      (libsource (lib "eagle-import") (part "DIODESOD-123"))
    )
    (comp (ref "D9")
      (value "DIODESOD-123")
      (footprint "eagle-import:SOD-123")
      (libsource (lib "eagle-import") (part "DIODESOD-123"))
    )
    (comp (ref "JP2")
      (value "VIB_MOTOR, 619-28821")
      (footprint "eagle-import:1X02")
      (libsource (lib "eagle-import") (part "PINHD-1X2"))
    )
    (comp (ref "Q3")
      (value "DMN3023L-7")
      (footprint "eagle-import:SOT23")
      (libsource (lib "eagle-import") (part "BSS123"))
    )
    (comp (ref "R4")
      (value "47k")
      (footprint "eagle-import:M0805")
      (libsource (lib "eagle-import") (part "R-EU_M0805"))
    )
    (comp (ref "R5")
      (value "10k")
      (footprint "eagle-import:M0805")
      (libsource (lib "eagle-import") (part "R-EU_M0805"))
    )
    (comp (ref "R6")
      (value "10k")
      (footprint "eagle-import:M0805")
      (libsource (lib "eagle-import") (part "R-EU_M0805"))
    )
    (comp (ref "R7")
      (value "10k")
      (footprint "eagle-import:M0805")
      (libsource (lib "eagle-import") (part "R-EU_M0805"))
    )
    (comp (ref "R8")
      (value "10k")
      (footprint "eagle-import:M0805")
      (libsource (lib "eagle-import") (part "R-EU_M0805"))
    )
    (comp (ref "R12")
      (value "10k")
      (footprint "eagle-import:M0805")
      (libsource (lib "eagle-import") (part "R-EU_M0805"))
    )
    (comp (ref "R13")
      (value "10k")
      (footprint "eagle-import:M0805")
      (libsource (lib "eagle-import") (part "R-EU_M0805"))
    )
    (comp (ref "R16")
      (value "10k")
      (footprint "eagle-import:M0805")
      (libsource (lib "eagle-import") (part "R-EU_M0805"))
    )
    (comp (ref "R17")
      (value "10k")
      (footprint "eagle-import:M0805")
      (libsource (lib "eagle-import") (part "R-EU_M0805"))
    )
    (comp (ref "R25")
      (value "100k")
      (footprint "eagle-import:M0805")
      (libsource (lib "eagle-import") (part "R-EU_M0805"))
    )
    (comp (ref "R59")
      (value "10k")
      (footprint "eagle-import:M0805")
      (libsource (lib "eagle-import") (part "R-EU_M0805"))
    )
    (comp (ref "S1")
      (value "TL3305")
      (footprint "eagle-import:SMD_SWITCH")
      (libsource (lib "eagle-import") (part "TL3305"))
    )
    (comp (ref "S2")
      (value "TL3305")
      (footprint "eagle-import:SMD_SWITCH")
      (libsource (lib "eagle-import") (part "TL3305"))
    )
    (comp (ref "S3")
      (value "TL3305")
      (footprint "eagle-import:SMD_SWITCH")
      (libsource (lib "eagle-import") (part "TL3305"))
    )
    (comp (ref "S4")
      (value "TL3305")
      (footprint "eagle-import:SMD_SWITCH")
      (libsource (lib "eagle-import") (part "TL3305"))
    )
    (comp (ref "S5")
      (value "TL3305")
      (footprint "eagle-import:SMD_SWITCH")
      (libsource (lib "eagle-import") (part "TL3305"))
    )
    (comp (ref "3V3")
      (value "PTR1B1,27")
      (footprint "eagle-import:B1,27")
      (libsource (lib "eagle-import") (part "PTR1B1,27"))
    )
    (comp (ref "B1")
      (value "BLM18KG601SN1D")
      (footprint "eagle-import:L0603")
      (libsource (lib "eagle-import") (part "B-EU_B0603"))
    )
    (comp (ref "BAT_ADC")
      (value "PTR1B1,27")
      (footprint "eagle-import:B1,27")
      (libsource (lib "eagle-import") (part "PTR1B1,27"))
    )
    (comp (ref "BT_RX")
      (value "PTR1B1,27")
      (footprint "eagle-import:B1,27")
      (libsource (lib "eagle-import") (part "PTR1B1,27"))
    )
    (comp (ref "BT_TX")
      (value "PTR1B1,27")
      (footprint "eagle-import:B1,27")
      (libsource (lib "eagle-import") (part "PTR1B1,27"))
    )
    (comp (ref "C4")
      (value "100nF")
      (footprint "eagle-import:C0805")
      (libsource (lib "eagle-import") (part "C-EUC0805"))
    )
    (comp (ref "C5")
      (value "100nF")
      (footprint "eagle-import:C0805")
      (libsource (lib "eagle-import") (part "C-EUC0805"))
    )
    (comp (ref "C6")
      (value "100nF")
      (footprint "eagle-import:C0805")
      (libsource (lib "eagle-import") (part "C-EUC0805"))
    )
    (comp (ref "C7")
      (value "100nF")
      (footprint "eagle-import:C0805")
      (libsource (lib "eagle-import") (part "C-EUC0805"))
    )
    (comp (ref "C8")
      (value "100nF")
      (footprint "eagle-import:C0805")
      (libsource (lib "eagle-import") (part "C-EUC0805"))
    )
    (comp (ref "C9")
      (value "10uF")
      (footprint "eagle-import:C1206")
      (libsource (lib "eagle-import") (part "C-EUC1206"))
    )
    (comp (ref "C10")
      (value "1uF")
      (footprint "eagle-import:C0805")
      (libsource (lib "eagle-import") (part "C-EUC0805"))
    )
    (comp (ref "C14")
      (value "27p")
      (footprint "eagle-import:C0805")
      (libsource (lib "eagle-import") (part "C-EUC0805"))
    )
    (comp (ref "C15")
      (value "27p")
      (footprint "eagle-import:C0805")
      (libsource (lib "eagle-import") (part "C-EUC0805"))
    )
    (comp (ref "C16")
      (value "100nF")
      (footprint "eagle-import:C0805")
      (libsource (lib "eagle-import") (part "C-EUC0805"))
    )
    (comp (ref "GPS>")
      (value "PINHD-1X8")
      (footprint "eagle-import:1X08")
      (libsource (lib "eagle-import") (part "PINHD-1X8"))
    )
    (comp (ref "LED2")
      (value "GREEN")
      (footprint "eagle-import:CHIP-LED0805")
      (libsource (lib "eagle-import") (part "LEDCHIP-LED0805"))
    )
    (comp (ref "LED3")
      (value "BLUE")
      (footprint "eagle-import:CHIP-LED0805")
      (libsource (lib "eagle-import") (part "LEDCHIP-LED0805"))
    )
    (comp (ref "LED4")
      (value "WHITE")
      (footprint "eagle-import:CHIP-LED0805")
      (libsource (lib "eagle-import") (part "LEDCHIP-LED0805"))
    )
    (comp (ref "LED5")
      (value "RED")
      (footprint "eagle-import:CHIP-LED0805")
      (libsource (lib "eagle-import") (part "LEDCHIP-LED0805"))
    )
    (comp (ref "LED6")
      (value "GREEN")
      (footprint "eagle-import:CHIP-LED0805")
      (libsource (lib "eagle-import") (part "LEDCHIP-LED0805"))
    )
    (comp (ref "LED7")
      (value "GREEN")
      (footprint "eagle-import:CHIP-LED0805")
      (libsource (lib "eagle-import") (part "LEDCHIP-LED0805"))
    )
    (comp (ref "LED8")
      (value "GREEN")
      (footprint "eagle-import:CHIP-LED0805")
      (libsource (lib "eagle-import") (part "LEDCHIP-LED0805"))
    )
    (comp (ref "LED9")
      (value "RED")
      (footprint "eagle-import:CHIP-LED0805")
      (libsource (lib "eagle-import") (part "LEDCHIP-LED0805"))
    )
    (comp (ref "LED10")
      (value "YELLOW")
      (footprint "eagle-import:CHIP-LED0805")
      (libsource (lib "eagle-import") (part "LEDCHIP-LED0805"))
    )
    (comp (ref "NRST_MCU")
      (value "PTR1B1,27")
      (footprint "eagle-import:B1,27")
      (libsource (lib "eagle-import") (part "PTR1B1,27"))
    )
    (comp (ref "PR0>")
      (value "SWD")
      (footprint "eagle-import:1X05")
      (libsource (lib "eagle-import") (part "PINHD-1X5"))
    )
    (comp (ref "Q1")
      (value "8MHz / LFXTAL020423Reel")
      (footprint "eagle-import:HC49UP")
      (libsource (lib "eagle-import") (part "crystal_CRYSTALHC49UP"))
    )
    (comp (ref "R9")
      (value "220R")
      (footprint "eagle-import:M0805")
      (libsource (lib "eagle-import") (part "R-EU_M0805"))
    )
    (comp (ref "R10")
      (value "470R")
      (footprint "eagle-import:M0805")
      (libsource (lib "eagle-import") (part "R-EU_M0805"))
    )
    (comp (ref "R11")
      (value "470R")
      (footprint "eagle-import:M0805")
      (libsource (lib "eagle-import") (part "R-EU_M0805"))
    )
    (comp (ref "R14")
      (value "470R")
      (footprint "eagle-import:M0805")
      (libsource (lib "eagle-import") (part "R-EU_M0805"))
    )
    (comp (ref "R15")
      (value "470R")
      (footprint "eagle-import:M0805")
      (libsource (lib "eagle-import") (part "R-EU_M0805"))
    )
    (comp (ref "R18")
      (value "470R")
      (footprint "eagle-import:M0805")
      (libsource (lib "eagle-import") (part "R-EU_M0805"))
    )
    (comp (ref "R19")
      (value "470R")
      (footprint "eagle-import:M0805")
      (libsource (lib "eagle-import") (part "R-EU_M0805"))
    )
    (comp (ref "R20")
      (value "470R")
      (footprint "eagle-import:M0805")
      (libsource (lib "eagle-import") (part "R-EU_M0805"))
    )
    (comp (ref "R21")
      (value "470R")
      (footprint "eagle-import:M0805")
      (libsource (lib "eagle-import") (part "R-EU_M0805"))
    )
    (comp (ref "R22")
      (value "470R")
      (footprint "eagle-import:M0805")
      (libsource (lib "eagle-import") (part "R-EU_M0805"))
    )
    (comp (ref "SWD_RXD")
      (value "PTR1B1,27")
      (footprint "eagle-import:B1,27")
      (libsource (lib "eagle-import") (part "PTR1B1,27"))
    )
    (comp (ref "SWD_TXD")
      (value "PTR1B1,27")
      (footprint "eagle-import:B1,27")
      (libsource (lib "eagle-import") (part "PTR1B1,27"))
    )
    (comp (ref "U2")
      (value "STM32L073RZ")
      (footprint "eagle-import:LQFP64-10X10MM")
      (fields (field (name "MANUFACTURER_PART_NUMBER") "stm32l0x3rl"))
      (libsource (lib "eagle-import") (part "STM32L0X3RL"))
    )
    (comp (ref "BAT")
      (value "PINHD-1X5")
      (footprint "eagle-import:1X05")
      (libsource (lib "eagle-import") (part "PINHD-1X5"))
    )
    (comp (ref "C38")
      (value "100nF")
      (footprint "eagle-import:C0805K")
      (libsource (lib "eagle-import") (part "C-EUC0805K"))
    )
    (comp (ref "C39")
      (value "100nF")
      (footprint "eagle-import:C0805K")
      (libsource (lib "eagle-import") (part "C-EUC0805K"))
    )
    (comp (ref "C40")
      (value "100nF")
      (footprint "eagle-import:C0805K")
      (libsource (lib "eagle-import") (part "C-EUC0805K"))
    )
    (comp (ref "C41")
      (value "100nF")
      (footprint "eagle-import:C0805K")
      (libsource (lib "eagle-import") (part "C-EUC0805K"))
    )
    (comp (ref "C42")
      (value "1uF")
      (footprint "eagle-import:C0805K")
      (libsource (lib "eagle-import") (part "C-EUC0805K"))
    )
    (comp (ref "C43")
      (value "1uF")
      (footprint "eagle-import:C0805K")
      (libsource (lib "eagle-import") (part "C-EUC0805K"))
    )
    (comp (ref "C44")
      (value "100nF")
      (footprint "eagle-import:C0805K")
      (libsource (lib "eagle-import") (part "C-EUC0805K"))
    )
    (comp (ref "C45")
      (value "100nF")
      (footprint "eagle-import:C0805K")
      (libsource (lib "eagle-import") (part "C-EUC0805K"))
    )
    (comp (ref "C46")
      (value "100nF")
      (footprint "eagle-import:C0805K")
      (libsource (lib "eagle-import") (part "C-EUC0805K"))
    )
    (comp (ref "D6")
      (value "Zener 16V MMSZ5246BS-7-F")
      (footprint "eagle-import:SOD323-R")
      (libsource (lib "eagle-import") (part "diode-1_DIODE-SOD323-R"))
    )
    (comp (ref "D7")
      (value "100V, BAS16J,135")
      (footprint "eagle-import:SOD323-R")
      (libsource (lib "eagle-import") (part "diode-1_DIODE-SOD323-R"))
    )
    (comp (ref "Q5")
      (value "CSD18534Q5A")
      (footprint "eagle-import:TRANS_CSD18534Q5A")
      (fields (field (name "MF") "Texas Instruments"))
      (libsource (lib "eagle-import") (part "CSD18534Q5A"))
    )
    (comp (ref "Q6")
      (value "CSD18534Q5A")
      (footprint "eagle-import:TRANS_CSD18534Q5A")
      (fields (field (name "MF") "Texas Instruments"))
      (libsource (lib "eagle-import") (part "CSD18534Q5A"))
    )
    (comp (ref "R30")
      (value "1k")
      (footprint "eagle-import:M0805")
      (libsource (lib "eagle-import") (part "R-EU_M0805"))
    )
    (comp (ref "R31")
      (value "1k")
      (footprint "eagle-import:M0805")
      (libsource (lib "eagle-import") (part "R-EU_M0805"))
    )
    (comp (ref "R32")
      (value "1k")
      (footprint "eagle-import:M0805")
      (libsource (lib "eagle-import") (part "R-EU_M0805"))
    )
    (comp (ref "R33")
      (value "1k")
      (footprint "eagle-import:M0805")
      (libsource (lib "eagle-import") (part "R-EU_M0805"))
    )
    (comp (ref "R34")
      (value "1k")
      (footprint "eagle-import:M0805")
      (libsource (lib "eagle-import") (part "R-EU_M0805"))
    )
    (comp (ref "R35")
      (value "10k")
      (footprint "eagle-import:M0805")
      (libsource (lib "eagle-import") (part "R-EU_M0805"))
    )
    (comp (ref "R36")
      (value "20mR")
      (footprint "eagle-import:R2512")
      (libsource (lib "eagle-import") (part "R-EU_R2512"))
    )
    (comp (ref "R37")
      (value "100R")
      (footprint "eagle-import:M0805")
      (libsource (lib "eagle-import") (part "R-EU_M0805"))
    )
    (comp (ref "R38")
      (value "100R")
      (footprint "eagle-import:M0805")
      (libsource (lib "eagle-import") (part "R-EU_M0805"))
    )
    (comp (ref "R39")
      (value "10M")
      (footprint "eagle-import:M0805")
      (libsource (lib "eagle-import") (part "R-EU_M0805"))
    )
    (comp (ref "R40")
      (value "5k1")
      (footprint "eagle-import:M0805")
      (libsource (lib "eagle-import") (part "R-EU_M0805"))
    )
    (comp (ref "R41")
      (value "3M3")
      (footprint "eagle-import:M0805")
      (libsource (lib "eagle-import") (part "R-EU_M0805"))
    )
    (comp (ref "R42")
      (value "1M")
      (footprint "eagle-import:M0805")
      (libsource (lib "eagle-import") (part "R-EU_M0805"))
    )
    (comp (ref "R43")
      (value "5k1")
      (footprint "eagle-import:M0805")
      (libsource (lib "eagle-import") (part "R-EU_M0805"))
    )
    (comp (ref "R44")
      (value "470k")
      (footprint "eagle-import:M0805")
      (libsource (lib "eagle-import") (part "R-EU_M0805"))
    )
    (comp (ref "R62")
      (value "NTC 103AT")
      (footprint "eagle-import:M0805")
      (libsource (lib "eagle-import") (part "R-EU_M0805"))
    )
    (comp (ref "U5")
      (value "BQ7790504")
      (footprint "eagle-import:TSSOP-20_6MM")
      (libsource (lib "eagle-import") (part "BQ77904"))
    )
  )
  (nets
    (net (code "1") (name "+3V3") (class "Default")
      (node (ref "3V3") (pin "TP") (pinfunction "TP_TP") (pintype "input"))
      (node (ref "B1") (pin "1") (pinfunction "1_1") (pintype "passive"))
      (node (ref "B3") (pin "1") (pinfunction "1_1") (pintype "passive"))
      (node (ref "B4") (pin "1") (pinfunction "1_1") (pintype "passive"))
      (node (ref "B5") (pin "1") (pinfunction "1_1") (pintype "passive"))
      (node (ref "B6") (pin "1") (pinfunction "1_1") (pintype "passive"))
      (node (ref "B7") (pin "1") (pinfunction "1_1") (pintype "passive"))
      (node (ref "C60") (pin "+") (pinfunction "+_+") (pintype "passive"))
      (node (ref "C7") (pin "1") (pinfunction "1_1") (pintype "passive"))
      (node (ref "GPS>") (pin "1") (pinfunction "1_1") (pintype "passive"))
      (node (ref "IC6") (pin "TAB") (pinfunction "OUT_TAB") (pintype "passive"))
      (node (ref "PR0>") (pin "4") (pinfunction "4_4") (pintype "passive"))
      (node (ref "Q2") (pin "C") (pinfunction "C_C") (pintype "passive"))
      (node (ref "R2") (pin "2") (pinfunction "2_2") (pintype "passive"))
      (node (ref "R23") (pin "1") (pinfunction "1_1") (pintype "passive"))
      (node (ref "R24") (pin "1") (pinfunction "1_1") (pintype "passive"))
      (node (ref "R4") (pin "1") (pinfunction "1_1") (pintype "passive"))
      (node (ref "R47") (pin "1") (pinfunction "1_1") (pintype "passive"))
      (node (ref "R57") (pin "1") (pinfunction "1_1") (pintype "passive"))
      (node (ref "S2") (pin "P$1") (pinfunction "SL1_P$1") (pintype "passive"))
      (node (ref "S2") (pin "P$2") (pinfunction "SL2_P$2") (pintype "passive"))
      (node (ref "S3") (pin "P$1") (pinfunction "SL1_P$1") (pintype "passive"))
      (node (ref "S3") (pin "P$2") (pinfunction "SL2_P$2") (pintype "passive"))
      (node (ref "S4") (pin "P$1") (pinfunction "SL1_P$1") (pintype "passive"))
      (node (ref "S4") (pin "P$2") (pinfunction "SL2_P$2") (pintype "passive"))
      (node (ref "S5") (pin "P$1") (pinfunction "SL1_P$1") (pintype "passive"))
      (node (ref "S5") (pin "P$2") (pinfunction "SL2_P$2") (pintype "passive"))
      (node (ref "U2") (pin "48") (pinfunction "VDD_USB_48") (pintype "power_in"))
      (node (ref "U3") (pin "4") (pinfunction "N_RST_4") (pintype "input"))
    )
    (net (code "2") (name "+12V") (class "Default")
      (node (ref "C54") (pin "+") (pinfunction "+_+") (pintype "passive"))
      (node (ref "IC3") (pin "TAB") (pinfunction "OUT_TAB") (pintype "passive"))
      (node (ref "R53") (pin "1") (pinfunction "1_1") (pintype "passive"))
      (node (ref "U$2") (pin "2") (pinfunction "DRAIN_VOLTAGE_2") (pintype "bidirectional"))
    )
    (net (code "3") (name "10V_INTERMEDIATE") (class "Default")
      (node (ref "C57") (pin "+") (pinfunction "+_+") (pintype "passive"))
      (node (ref "C59") (pin "+") (pinfunction "+_+") (pintype "passive"))
      (node (ref "IC5") (pin "TAB") (pinfunction "OUT_TAB") (pintype "passive"))
      (node (ref "IC6") (pin "2") (pinfunction "IN_2") (pintype "input"))
      (node (ref "R55") (pin "1") (pinfunction "1_1") (pintype "passive"))
    )
    (net (code "4") (name "ANT_N") (class "Default")
      (node (ref "C29") (pin "1") (pinfunction "1_1") (pintype "passive"))
      (node (ref "IC4") (pin "3") (pinfunction "ANTN_3") (pintype "output"))
      (node (ref "L1") (pin "2") (pinfunction "2_2") (pintype "passive"))
      (node (ref "L2") (pin "2") (pinfunction "2_2") (pintype "passive"))
    )
    (net (code "5") (name "ANT_P") (class "Default")
      (node (ref "C30") (pin "2") (pinfunction "2_2") (pintype "passive"))
      (node (ref "IC4") (pin "2") (pinfunction "ANTP_2") (pintype "output"))
      (node (ref "L3") (pin "1") (pinfunction "1_1") (pintype "passive"))
      (node (ref "L4") (pin "2") (pinfunction "2_2") (pintype "passive"))
    )
    (net (code "6") (name "BAT_ADC") (class "Default")
      (node (ref "BAT_ADC") (pin "TP") (pinfunction "TP_TP") (pintype "input"))
      (node (ref "R60") (pin "1") (pinfunction "1_1") (pintype "passive"))
      (node (ref "R61") (pin "2") (pinfunction "2_2") (pintype "passive"))
      (node (ref "U2") (pin "15") (pinfunction "PA1_15") (pintype "bidirectional"))
    )
    (net (code "7") (name "BAT_PACK_POS") (class "Default")
      (node (ref "BAT") (pin "1") (pinfunction "1_1") (pintype "passive"))
      (node (ref "BAT_PACK_POS") (pin "TP") (pinfunction "TP_TP") (pintype "input"))
      (node (ref "C51") (pin "+") (pinfunction "+_+") (pintype "passive"))
      (node (ref "C52") (pin "+") (pinfunction "+_+") (pintype "passive"))
      (node (ref "D10") (pin "C") (pinfunction "C_C") (pintype "passive"))
      (node (ref "JP3") (pin "1") (pinfunction "1_1") (pintype "passive"))
      (node (ref "R30") (pin "1") (pinfunction "1_1") (pintype "passive"))
      (node (ref "R34") (pin "1") (pinfunction "1_1") (pintype "passive"))
      (node (ref "R51") (pin "2") (pinfunction "2_2") (pintype "passive"))
    )
    (net (code "8") (name "BTN_1") (class "Default")
      (node (ref "BTN_1") (pin "TP") (pinfunction "TP_TP") (pintype "input"))
      (node (ref "D2") (pin "A") (pinfunction "A_A") (pintype "passive"))
      (node (ref "R6") (pin "2") (pinfunction "2_2") (pintype "passive"))
      (node (ref "R7") (pin "1") (pinfunction "1_1") (pintype "passive"))
      (node (ref "S2") (pin "P$3") (pinfunction "SR1_P$3") (pintype "passive"))
      (node (ref "S2") (pin "P$4") (pinfunction "SR2_P$4") (pintype "passive"))
      (node (ref "U2") (pin "33") (pinfunction "PB12_33") (pintype "bidirectional"))
    )
    (net (code "9") (name "BTN_2") (class "Default")
      (node (ref "BTN_2") (pin "TP") (pinfunction "TP_TP") (pintype "input"))
      (node (ref "D3") (pin "A") (pinfunction "A_A") (pintype "passive"))
      (node (ref "R5") (pin "2") (pinfunction "2_2") (pintype "passive"))
      (node (ref "R8") (pin "1") (pinfunction "1_1") (pintype "passive"))
      (node (ref "S3") (pin "P$3") (pinfunction "SR1_P$3") (pintype "passive"))
      (node (ref "S3") (pin "P$4") (pinfunction "SR2_P$4") (pintype "passive"))
      (node (ref "U2") (pin "38") (pinfunction "PC7_38") (pintype "bidirectional"))
    )
    (net (code "10") (name "BTN_3") (class "Default")
      (node (ref "BTN_3") (pin "TP") (pinfunction "TP_TP") (pintype "input"))
      (node (ref "D4") (pin "A") (pinfunction "A_A") (pintype "passive"))
      (node (ref "R12") (pin "2") (pinfunction "2_2") (pintype "passive"))
      (node (ref "R13") (pin "1") (pinfunction "1_1") (pintype "passive"))
      (node (ref "S4") (pin "P$3") (pinfunction "SR1_P$3") (pintype "passive"))
      (node (ref "S4") (pin "P$4") (pinfunction "SR2_P$4") (pintype "passive"))
      (node (ref "U2") (pin "39") (pinfunction "PC8_39") (pintype "bidirectional"))
    )
    (net (code "11") (name "BTN_4") (class "Default")
      (node (ref "BTN_4") (pin "TP") (pinfunction "TP_TP") (pintype "input"))
      (node (ref "D5") (pin "A") (pinfunction "A_A") (pintype "passive"))
      (node (ref "R16") (pin "2") (pinfunction "2_2") (pintype "passive"))
      (node (ref "R17") (pin "1") (pinfunction "1_1") (pintype "passive"))
      (node (ref "S5") (pin "P$3") (pinfunction "SR1_P$3") (pintype "passive"))
      (node (ref "S5") (pin "P$4") (pinfunction "SR2_P$4") (pintype "passive"))
      (node (ref "U2") (pin "40") (pinfunction "PC9_40") (pintype "bidirectional"))
    )
    (net (code "12") (name "BT_HCI_RXD") (class "Default")
      (node (ref "BT_RX") (pin "TP") (pinfunction "TP_TP") (pintype "input"))
      (node (ref "CONFIG_INTERFACE_TEST_POINT") (pin "3") (pinfunction "3_3") (pintype "passive"))
      (node (ref "IC2") (pin "22") (pinfunction "HCI_RXD_22") (pintype "bidirectional"))
      (node (ref "U2") (pin "42") (pinfunction "PA9_42") (pintype "bidirectional"))
    )
    (net (code "13") (name "BT_HCI_TXD") (class "Default")
      (node (ref "BT_TX") (pin "TP") (pinfunction "TP_TP") (pintype "input"))
      (node (ref "CONFIG_INTERFACE_TEST_POINT") (pin "4") (pinfunction "4_4") (pintype "passive"))
      (node (ref "IC2") (pin "23") (pinfunction "HCI_TXD_23") (pintype "bidirectional"))
      (node (ref "U2") (pin "43") (pinfunction "PA10_43") (pintype "bidirectional"))
    )
    (net (code "14") (name "BT_NRST") (class "Default")
      (node (ref "IC2") (pin "21") (pinfunction "RST_N_21") (pintype "bidirectional"))
      (node (ref "R3") (pin "2") (pinfunction "2_2") (pintype "passive"))
      (node (ref "U1") (pin "1") (pinfunction "VOUT_1") (pintype "passive"))
    )
    (net (code "15") (name "BT_P2_0_MODE") (class "Default")
      (node (ref "CONFIG_INTERFACE_TEST_POINT") (pin "1") (pinfunction "1_1") (pintype "passive"))
      (node (ref "IC2") (pin "18") (pinfunction "P2_0/MODE_18") (pintype "bidirectional"))
    )
    (net (code "16") (name "CHARGER_CH_PRECH") (class "Default")
      (node (ref "Q7") (pin "1") (pinfunction "G_1") (pintype "passive"))
      (node (ref "R1") (pin "1") (pinfunction "1_1") (pintype "passive"))
      (node (ref "U2") (pin "54") (pinfunction "PD2_54") (pintype "bidirectional"))
    )
    (net (code "17") (name "CHARGER_SS") (class "Default")
      (node (ref "IC1") (pin "6") (pinfunction "S/S_6") (pintype "bidirectional"))
      (node (ref "R2") (pin "1") (pinfunction "1_1") (pintype "passive"))
      (node (ref "U2") (pin "53") (pinfunction "PC12_53") (pintype "bidirectional"))
    )
    (net (code "18") (name "GND") (class "Default")
      (node (ref "C10") (pin "1") (pinfunction "1_1") (pintype "passive"))
      (node (ref "C11") (pin "1") (pinfunction "1_1") (pintype "passive"))
      (node (ref "C12") (pin "1") (pinfunction "1_1") (pintype "passive"))
      (node (ref "C13") (pin "1") (pinfunction "1_1") (pintype "passive"))
      (node (ref "C14") (pin "2") (pinfunction "2_2") (pintype "passive"))
      (node (ref "C15") (pin "2") (pinfunction "2_2") (pintype "passive"))
      (node (ref "C16") (pin "1") (pinfunction "1_1") (pintype "passive"))
      (node (ref "C17") (pin "1") (pinfunction "1_1") (pintype "passive"))
      (node (ref "C18") (pin "1") (pinfunction "1_1") (pintype "passive"))
      (node (ref "C19") (pin "2") (pinfunction "22_2") (pintype "passive"))
      (node (ref "C20") (pin "2") (pinfunction "2_2") (pintype "passive"))
      (node (ref "C21") (pin "1") (pinfunction "1_1") (pintype "passive"))
      (node (ref "C22") (pin "1") (pinfunction "1_1") (pintype "passive"))
      (node (ref "C23") (pin "1") (pinfunction "1_1") (pintype "passive"))
      (node (ref "C24") (pin "1") (pinfunction "1_1") (pintype "passive"))
      (node (ref "C25") (pin "1") (pinfunction "1_1") (pintype "passive"))
      (node (ref "C26") (pin "1") (pinfunction "1_1") (pintype "passive"))
      (node (ref "C27") (pin "1") (pinfunction "1_1") (pintype "passive"))
      (node (ref "C32") (pin "1") (pinfunction "1_1") (pintype "passive"))
      (node (ref "C33") (pin "2") (pinfunction "2_2") (pintype "passive"))
      (node (ref "C34") (pin "1") (pinfunction "1_1") (pintype "passive"))
      (node (ref "C36") (pin "1") (pinfunction "1_1") (pintype "passive"))
      (node (ref "C37") (pin "1") (pinfunction "1_1") (pintype "passive"))
      (node (ref "C4") (pin "2") (pinfunction "2_2") (pintype "passive"))
      (node (ref "C47") (pin "1") (pinfunction "1_1") (pintype "passive"))
      (node (ref "C48") (pin "-") (pinfunction "-_-") (pintype "passive"))
      (node (ref "C49") (pin "1") (pinfunction "1_1") (pintype "passive"))
      (node (ref "C5") (pin "1") (pinfunction "1_1") (pintype "passive"))
      (node (ref "C51") (pin "-") (pinfunction "-_-") (pintype "passive"))
      (node (ref "C52") (pin "-") (pinfunction "-_-") (pintype "passive"))
      (node (ref "C53") (pin "-") (pinfunction "-_-") (pintype "passive"))
      (node (ref "C54") (pin "-") (pinfunction "-_-") (pintype "passive"))
      (node (ref "C55") (pin "-") (pinfunction "-_-") (pintype "passive"))
      (node (ref "C56") (pin "-") (pinfunction "-_-") (pintype "passive"))
      (node (ref "C57") (pin "-") (pinfunction "-_-") (pintype "passive"))
      (node (ref "C58") (pin "-") (pinfunction "-_-") (pintype "passive"))
      (node (ref "C59") (pin "-") (pinfunction "-_-") (pintype "passive"))
      (node (ref "C6") (pin "1") (pinfunction "1_1") (pintype "passive"))
      (node (ref "C60") (pin "-") (pinfunction "-_-") (pintype "passive"))
      (node (ref "C61") (pin "-") (pinfunction "-_-") (pintype "passive"))
      (node (ref "C7") (pin "2") (pinfunction "2_2") (pintype "passive"))
      (node (ref "C8") (pin "2") (pinfunction "2_2") (pintype "passive"))
      (node (ref "C9") (pin "2") (pinfunction "2_2") (pintype "passive"))
      (node (ref "CONFIG_INTERFACE_TEST_POINT") (pin "5") (pinfunction "5_5") (pintype "passive"))
      (node (ref "D6") (pin "A") (pinfunction "A_A") (pintype "passive"))
      (node (ref "FB3") (pin "1") (pinfunction "1_1") (pintype "passive"))
      (node (ref "FB4") (pin "1") (pinfunction "1_1") (pintype "passive"))
      (node (ref "GPS>") (pin "2") (pinfunction "2_2") (pintype "passive"))
      (node (ref "IC1") (pin "4") (pinfunction "GND_4") (pintype "bidirectional"))
      (node (ref "IC2") (pin "1") (pinfunction "GND(1)_1") (pintype "bidirectional"))
      (node (ref "IC2") (pin "2") (pinfunction "GND(2)_2") (pintype "bidirectional"))
      (node (ref "IC2") (pin "3") (pinfunction "GND(3)_3") (pintype "bidirectional"))
      (node (ref "IC2") (pin "31") (pinfunction "GND(4)_31") (pintype "bidirectional"))
      (node (ref "IC2") (pin "32") (pinfunction "GND(5)_32") (pintype "bidirectional"))
      (node (ref "IC2") (pin "33") (pinfunction "GND(6)_33") (pintype "bidirectional"))
      (node (ref "IC4") (pin "PAD") (pinfunction "GND_PAD_PAD") (pintype "power_in"))
      (node (ref "J1") (pin "GND") (pinfunction "GND_GND") (pintype "power_in"))
      (node (ref "J1") (pin "SHIELD1") (pinfunction "SHIELD_SHIELD1") (pintype "bidirectional"))
      (node (ref "J1") (pin "SHIELD2") (pinfunction "SHIELD_SHIELD2") (pintype "bidirectional"))
      (node (ref "J1") (pin "SHIELD3") (pinfunction "SHIELD_SHIELD3") (pintype "bidirectional"))
      (node (ref "J3") (pin "GND") (pinfunction "GND_GND") (pintype "bidirectional"))
      (node (ref "J4") (pin "GND") (pinfunction "GND_GND") (pintype "power_in"))
      (node (ref "J4") (pin "SHIELD1") (pinfunction "SHIELD_SHIELD1") (pintype "bidirectional"))
      (node (ref "J4") (pin "SHIELD2") (pinfunction "SHIELD_SHIELD2") (pintype "bidirectional"))
      (node (ref "J4") (pin "SHIELD3") (pinfunction "SHIELD_SHIELD3") (pintype "bidirectional"))
      (node (ref "L5") (pin "1") (pinfunction "1_1") (pintype "passive"))
      (node (ref "LED10") (pin "C") (pinfunction "C_C") (pintype "passive"))
      (node (ref "LED2") (pin "C") (pinfunction "C_C") (pintype "passive"))
      (node (ref "LED3") (pin "C") (pinfunction "C_C") (pintype "passive"))
      (node (ref "LED4") (pin "C") (pinfunction "C_C") (pintype "passive"))
      (node (ref "LED5") (pin "C") (pinfunction "C_C") (pintype "passive"))
      (node (ref "LED6") (pin "C") (pinfunction "C_C") (pintype "passive"))
      (node (ref "LED7") (pin "C") (pinfunction "C_C") (pintype "passive"))
      (node (ref "LED8") (pin "C") (pinfunction "C_C") (pintype "passive"))
      (node (ref "LED9") (pin "C") (pinfunction "C_C") (pintype "passive"))
      (node (ref "PR0>") (pin "1") (pinfunction "1_1") (pintype "passive"))
      (node (ref "Q3") (pin "2") (pinfunction "S_2") (pintype "passive"))
      (node (ref "Q6") (pin "1") (pinfunction "1_1") (pintype "passive"))
      (node (ref "Q6") (pin "2") (pinfunction "2_2") (pintype "passive"))
      (node (ref "Q6") (pin "3") (pinfunction "3_3") (pintype "passive"))
      (node (ref "Q7") (pin "2") (pinfunction "S_2") (pintype "passive"))
      (node (ref "R1") (pin "2") (pinfunction "2_2") (pintype "passive"))
      (node (ref "R13") (pin "2") (pinfunction "2_2") (pintype "passive"))
      (node (ref "R17") (pin "2") (pinfunction "2_2") (pintype "passive"))
      (node (ref "R25") (pin "2") (pinfunction "2_2") (pintype "passive"))
      (node (ref "R26") (pin "2") (pinfunction "2_2") (pintype "passive"))
      (node (ref "R28") (pin "2") (pinfunction "2_2") (pintype "passive"))
      (node (ref "R41") (pin "1") (pinfunction "1_1") (pintype "passive"))
      (node (ref "R44") (pin "2") (pinfunction "2_2") (pintype "passive"))
      (node (ref "R50") (pin "1") (pinfunction "1_1") (pintype "passive"))
      (node (ref "R52") (pin "1") (pinfunction "1_1") (pintype "passive"))
      (node (ref "R54") (pin "2") (pinfunction "2_2") (pintype "passive"))
      (node (ref "R56") (pin "2") (pinfunction "2_2") (pintype "passive"))
      (node (ref "R58") (pin "2") (pinfunction "2_2") (pintype "passive"))
      (node (ref "R61") (pin "1") (pinfunction "1_1") (pintype "passive"))
      (node (ref "R7") (pin "2") (pinfunction "2_2") (pintype "passive"))
      (node (ref "R8") (pin "2") (pinfunction "2_2") (pintype "passive"))
      (node (ref "S1") (pin "P$3") (pinfunction "SR1_P$3") (pintype "passive"))
      (node (ref "S1") (pin "P$4") (pinfunction "SR2_P$4") (pintype "passive"))
      (node (ref "U$2") (pin "5_L") (pinfunction "RF_GND_L_5_L") (pintype "bidirectional"))
      (node (ref "U$2") (pin "5_R") (pinfunction "RF_GND_R_5_R") (pintype "bidirectional"))
      (node (ref "U1") (pin "2") (pinfunction "VDD_2") (pintype "passive"))
      (node (ref "U2") (pin "12") (pinfunction "VSSA_12") (pintype "power_in"))
      (node (ref "U2") (pin "18") (pinfunction "VSS_2_18") (pintype "power_in"))
      (node (ref "U2") (pin "31") (pinfunction "VSS_3_31") (pintype "power_in"))
      (node (ref "U2") (pin "47") (pinfunction "VSS_4_47") (pintype "power_in"))
      (node (ref "U2") (pin "60") (pinfunction "BOOT0_60") (pintype "input"))
      (node (ref "U2") (pin "63") (pinfunction "VSS_63") (pintype "power_in"))
      (node (ref "U3") (pin "20") (pinfunction "VSS_20") (pintype "power_in"))
      (node (ref "U4") (pin "3") (pinfunction "GND_3") (pintype "passive"))
    )
    (net (code "19") (name "GPS_EXTINT") (class "Default")
      (node (ref "GPS>") (pin "5") (pinfunction "5_5") (pintype "passive"))
      (node (ref "U2") (pin "36") (pinfunction "PB15_36") (pintype "bidirectional"))
    )
    (net (code "20") (name "GPS_NRESET") (class "Default")
      (node (ref "GPS>") (pin "6") (pinfunction "6_6") (pintype "passive"))
      (node (ref "U2") (pin "37") (pinfunction "PC6_37") (pintype "bidirectional"))
    )
    (net (code "21") (name "GPS_RXD") (class "Default")
      (node (ref "GPS>") (pin "7") (pinfunction "7_7") (pintype "passive"))
      (node (ref "U2") (pin "51") (pinfunction "PC10_51") (pintype "bidirectional"))
    )
    (net (code "22") (name "GPS_SCL") (class "Default")
      (node (ref "GPS>") (pin "3") (pinfunction "3_3") (pintype "passive"))
      (node (ref "U2") (pin "34") (pinfunction "PB13_34") (pintype "bidirectional"))
    )
    (net (code "23") (name "GPS_SDA") (class "Default")
      (node (ref "GPS>") (pin "4") (pinfunction "4_4") (pintype "passive"))
      (node (ref "U2") (pin "35") (pinfunction "PB14_35") (pintype "bidirectional"))
    )
    (net (code "24") (name "GPS_TXD") (class "Default")
      (node (ref "GPS>") (pin "8") (pinfunction "8_8") (pintype "passive"))
      (node (ref "U2") (pin "52") (pinfunction "PC11_52") (pintype "bidirectional"))
    )
    (net (code "25") (name "IND_LED_B") (class "Default")
      (node (ref "R11") (pin "2") (pinfunction "2_2") (pintype "passive"))
      (node (ref "U2") (pin "26") (pinfunction "PB0_26") (pintype "bidirectional"))
    )
    (net (code "26") (name "IND_LED_G") (class "Default")
      (node (ref "R10") (pin "2") (pinfunction "2_2") (pintype "passive"))
      (node (ref "U2") (pin "25") (pinfunction "PC5_25") (pintype "bidirectional"))
    )
    (net (code "27") (name "IND_LED_R") (class "Default")
      (node (ref "R15") (pin "2") (pinfunction "2_2") (pintype "passive"))
      (node (ref "U2") (pin "28") (pinfunction "PB2_28") (pintype "bidirectional"))
    )
    (net (code "28") (name "IND_LED_W") (class "Default")
      (node (ref "R14") (pin "2") (pinfunction "2_2") (pintype "passive"))
      (node (ref "U2") (pin "27") (pinfunction "PB1_27") (pintype "bidirectional"))
    )
    (net (code "29") (name "INT_POWER") (class "Default")
      (node (ref "C21") (pin "2") (pinfunction "2_2") (pintype "passive"))
      (node (ref "C22") (pin "2") (pinfunction "2_2") (pintype "passive"))
      (node (ref "C23") (pin "2") (pinfunction "2_2") (pintype "passive"))
      (node (ref "C25") (pin "2") (pinfunction "2_2") (pintype "passive"))
      (node (ref "C26") (pin "2") (pinfunction "2_2") (pintype "passive"))
      (node (ref "C27") (pin "2") (pinfunction "2_2") (pintype "passive"))
      (node (ref "C29") (pin "2") (pinfunction "2_2") (pintype "passive"))
      (node (ref "C30") (pin "1") (pinfunction "1_1") (pintype "passive"))
      (node (ref "IC4") (pin "1") (pinfunction "VDD1_1") (pintype "power_in"))
      (node (ref "IC4") (pin "17") (pinfunction "VREG_17") (pintype "power_in"))
      (node (ref "IC4") (pin "4") (pinfunction "VDD2_4") (pintype "power_in"))
      (node (ref "L2") (pin "1") (pinfunction "1_1") (pintype "passive"))
      (node (ref "L3") (pin "2") (pinfunction "2_2") (pintype "passive"))
    )
    (net (code "30") (name "MCU_WAKEUP") (class "Default")
      (node (ref "D2") (pin "C") (pinfunction "C_C") (pintype "passive"))
      (node (ref "D3") (pin "C") (pinfunction "C_C") (pintype "passive"))
      (node (ref "D4") (pin "C") (pinfunction "C_C") (pintype "passive"))
      (node (ref "D5") (pin "C") (pinfunction "C_C") (pintype "passive"))
      (node (ref "D8") (pin "C") (pinfunction "C_C") (pintype "passive"))
      (node (ref "D9") (pin "C") (pinfunction "C_C") (pintype "passive"))
      (node (ref "U2") (pin "14") (pinfunction "PA0_14") (pintype "bidirectional"))
    )
    (net (code "31") (name "N$14") (class "Default")
      (node (ref "U2") (pin "41") (pinfunction "PA8_41") (pintype "bidirectional"))
    )
    (net (code "32") (name "N$78") (class "Default")
      (node (ref "B4") (pin "2") (pinfunction "2_2") (pintype "passive"))
      (node (ref "CONFIG_INTERFACE_TEST_POINT") (pin "2") (pinfunction "2_2") (pintype "passive"))
    )
    (net (code "33") (name "NRST") (class "Default")
      (node (ref "BTN_NRST") (pin "TP") (pinfunction "TP_TP") (pintype "input"))
      (node (ref "NRST_MCU") (pin "TP") (pinfunction "TP_TP") (pintype "input"))
      (node (ref "PR0>") (pin "5") (pinfunction "5_5") (pintype "passive"))
      (node (ref "R4") (pin "2") (pinfunction "2_2") (pintype "passive"))
      (node (ref "R59") (pin "2") (pinfunction "2_2") (pintype "passive"))
      (node (ref "S1") (pin "P$1") (pinfunction "SL1_P$1") (pintype "passive"))
      (node (ref "S1") (pin "P$2") (pinfunction "SL2_P$2") (pintype "passive"))
      (node (ref "U2") (pin "7") (pinfunction "NRST_7") (pintype "bidirectional"))
    )
    (net (code "34") (name "Net-(B5-Pad2)") (class "Default")
      (node (ref "B5") (pin "2") (pinfunction "2_2") (pintype "passive"))
      (node (ref "D1") (pin "C") (pinfunction "C_C") (pintype "passive"))
      (node (ref "JP2") (pin "1") (pinfunction "1_1") (pintype "passive"))
    )
    (net (code "35") (name "Net-(BAT-Pad2)") (class "Default")
      (node (ref "BAT") (pin "2") (pinfunction "2_2") (pintype "passive"))
      (node (ref "R31") (pin "1") (pinfunction "1_1") (pintype "passive"))
    )
    (net (code "36") (name "Net-(BAT-Pad3)") (class "Default")
      (node (ref "BAT") (pin "3") (pinfunction "3_3") (pintype "passive"))
      (node (ref "R32") (pin "1") (pinfunction "1_1") (pintype "passive"))
    )
    (net (code "37") (name "Net-(BAT-Pad4)") (class "Default")
      (node (ref "BAT") (pin "4") (pinfunction "4_4") (pintype "passive"))
      (node (ref "R33") (pin "1") (pinfunction "1_1") (pintype "passive"))
    )
    (net (code "38") (name "Net-(C11-Pad2)") (class "Default")
      (node (ref "C11") (pin "2") (pinfunction "2_2") (pintype "passive"))
      (node (ref "R59") (pin "1") (pinfunction "1_1") (pintype "passive"))
    )
    (net (code "39") (name "Net-(C12-Pad2)") (class "Default")
      (node (ref "C12") (pin "2") (pinfunction "2_2") (pintype "passive"))
      (node (ref "R6") (pin "1") (pinfunction "1_1") (pintype "passive"))
    )
    (net (code "40") (name "Net-(C13-Pad2)") (class "Default")
      (node (ref "C13") (pin "2") (pinfunction "2_2") (pintype "passive"))
      (node (ref "R5") (pin "1") (pinfunction "1_1") (pintype "passive"))
    )
    (net (code "41") (name "Net-(C15-Pad1)") (class "Default")
      (node (ref "C15") (pin "1") (pinfunction "1_1") (pintype "passive"))
      (node (ref "Q1") (pin "1") (pinfunction "1_1") (pintype "passive"))
      (node (ref "R9") (pin "1") (pinfunction "1_1") (pintype "passive"))
    )
    (net (code "42") (name "Net-(C17-Pad2)") (class "Default")
      (node (ref "C17") (pin "2") (pinfunction "2_2") (pintype "passive"))
      (node (ref "R12") (pin "1") (pinfunction "1_1") (pintype "passive"))
    )
    (net (code "43") (name "Net-(C18-Pad2)") (class "Default")
      (node (ref "C18") (pin "2") (pinfunction "2_2") (pintype "passive"))
      (node (ref "R16") (pin "1") (pinfunction "1_1") (pintype "passive"))
    )
    (net (code "44") (name "Net-(C19-11)") (class "Default")
      (node (ref "C19") (pin "1") (pinfunction "11_1") (pintype "passive"))
      (node (ref "U3") (pin "2") (pinfunction "OSC1_2") (pintype "input"))
    )
    (net (code "45") (name "Net-(C19-33)") (class "Default")
      (node (ref "C19") (pin "3") (pinfunction "33_3") (pintype "passive"))
      (node (ref "U3") (pin "3") (pinfunction "OSC2_3") (pintype "output"))
    )
    (net (code "46") (name "Net-(C28-Pad1)") (class "Default")
      (node (ref "C28") (pin "1") (pinfunction "1_1") (pintype "passive"))
      (node (ref "L4") (pin "1") (pinfunction "1_1") (pintype "passive"))
    )
    (net (code "47") (name "Net-(C28-Pad2)") (class "Default")
      (node (ref "C28") (pin "2") (pinfunction "2_2") (pintype "passive"))
      (node (ref "C33") (pin "1") (pinfunction "1_1") (pintype "passive"))
      (node (ref "C35") (pin "2") (pinfunction "2_2") (pintype "passive"))
      (node (ref "L5") (pin "2") (pinfunction "2_2") (pintype "passive"))
    )
    (net (code "48") (name "Net-(C31-Pad1)") (class "Default")
      (node (ref "C31") (pin "1") (pinfunction "1_1") (pintype "passive"))
      (node (ref "L1") (pin "1") (pinfunction "1_1") (pintype "passive"))
    )
    (net (code "49") (name "Net-(C31-Pad2)") (class "Default")
      (node (ref "C31") (pin "2") (pinfunction "2_2") (pintype "passive"))
      (node (ref "C32") (pin "2") (pinfunction "2_2") (pintype "passive"))
      (node (ref "C34") (pin "2") (pinfunction "2_2") (pintype "passive"))
      (node (ref "L6") (pin "1") (pinfunction "1_1") (pintype "passive"))
    )
    (net (code "50") (name "Net-(C35-Pad1)") (class "Default")
      (node (ref "C35") (pin "1") (pinfunction "1_1") (pintype "passive"))
      (node (ref "C36") (pin "2") (pinfunction "2_2") (pintype "passive"))
      (node (ref "L6") (pin "2") (pinfunction "2_2") (pintype "passive"))
      (node (ref "L7") (pin "1") (pinfunction "1_1") (pintype "passive"))
    )
    (net (code "51") (name "Net-(C47-Pad2)") (class "Default")
      (node (ref "C47") (pin "2") (pinfunction "2_2") (pintype "passive"))
      (node (ref "R45") (pin "2") (pinfunction "2_2") (pintype "passive"))
    )
    (net (code "52") (name "Net-(C63-Pad-)") (class "Default")
      (node (ref "C63") (pin "-") (pinfunction "-_-") (pintype "passive"))
      (node (ref "D10") (pin "A") (pinfunction "A_A") (pintype "passive"))
      (node (ref "L8") (pin "3") (pinfunction "3_3") (pintype "passive"))
    )
    (net (code "53") (name "Net-(D6-PadC)") (class "Default")
      (node (ref "D6") (pin "C") (pinfunction "C_C") (pintype "passive"))
      (node (ref "D7") (pin "C") (pinfunction "C_C") (pintype "passive"))
      (node (ref "Q6") (pin "4") (pinfunction "4_4") (pintype "passive"))
      (node (ref "R41") (pin "2") (pinfunction "2_2") (pintype "passive"))
      (node (ref "R42") (pin "1") (pinfunction "1_1") (pintype "passive"))
    )
    (net (code "54") (name "Net-(D7-PadA)") (class "Default")
      (node (ref "D7") (pin "A") (pinfunction "A_A") (pintype "passive"))
      (node (ref "R42") (pin "2") (pinfunction "2_2") (pintype "passive"))
      (node (ref "R43") (pin "2") (pinfunction "2_2") (pintype "passive"))
    )
    (net (code "55") (name "Net-(FB1-Pad1)") (class "Default")
      (node (ref "FB1") (pin "1") (pinfunction "1_1") (pintype "passive"))
      (node (ref "J2") (pin "VBUS") (pinfunction "VBUS_VBUS") (pintype "power_in"))
    )
    (net (code "56") (name "Net-(FB3-Pad2)") (class "Default")
      (node (ref "FB3") (pin "2") (pinfunction "2_2") (pintype "passive"))
      (node (ref "J2") (pin "GND") (pinfunction "GND_GND") (pintype "power_in"))
    )
    (net (code "57") (name "Net-(FB4-Pad2)") (class "Default")
      (node (ref "FB4") (pin "2") (pinfunction "2_2") (pintype "passive"))
      (node (ref "J2") (pin "SHIELD1") (pinfunction "SHIELD_SHIELD1") (pintype "bidirectional"))
      (node (ref "J2") (pin "SHIELD2") (pinfunction "SHIELD_SHIELD2") (pintype "bidirectional"))
      (node (ref "J2") (pin "SHIELD3") (pinfunction "SHIELD_SHIELD3") (pintype "bidirectional"))
    )
    (net (code "58") (name "Net-(IC1-IFB)") (class "Default")
      (node (ref "C49") (pin "2") (pinfunction "2_2") (pintype "passive"))
      (node (ref "IC1") (pin "3") (pinfunction "IFB_3") (pintype "bidirectional"))
      (node (ref "R48") (pin "2") (pinfunction "2_2") (pintype "passive"))
      (node (ref "R49") (pin "1") (pinfunction "1_1") (pintype "passive"))
    )
    (net (code "59") (name "Net-(IC1-VC)") (class "Default")
      (node (ref "IC1") (pin "1") (pinfunction "VC_1") (pintype "bidirectional"))
      (node (ref "R45") (pin "1") (pinfunction "1_1") (pintype "passive"))
    )
    (net (code "60") (name "Net-(IC1-VFB)") (class "Default")
      (node (ref "IC1") (pin "2") (pinfunction "VFB_2") (pintype "bidirectional"))
      (node (ref "R51") (pin "1") (pinfunction "1_1") (pintype "passive"))
      (node (ref "R52") (pin "2") (pinfunction "2_2") (pintype "passive"))
    )
    (net (code "61") (name "Net-(IC1-VIN)") (class "Default")
      (node (ref "C48") (pin "+") (pinfunction "+_+") (pintype "passive"))
      (node (ref "IC1") (pin "7") (pinfunction "VIN_7") (pintype "bidirectional"))
      (node (ref "J4") (pin "VBUS") (pinfunction "VBUS_VBUS") (pintype "power_in"))
      (node (ref "L8") (pin "1") (pinfunction "1_1") (pintype "passive"))
    )
    (net (code "62") (name "Net-(IC1-VSW)") (class "Default")
      (node (ref "C63") (pin "+") (pinfunction "+_+") (pintype "passive"))
      (node (ref "IC1") (pin "5") (pinfunction "VSW_5") (pintype "bidirectional"))
      (node (ref "L8") (pin "2") (pinfunction "2_2") (pintype "passive"))
    )
    (net (code "63") (name "Net-(IC2-P0_2{slash}LED)") (class "Default")
      (node (ref "IC2") (pin "30") (pinfunction "P0_2/LED_30") (pintype "bidirectional"))
      (node (ref "LED1") (pin "C") (pinfunction "C_C") (pintype "passive"))
    )
    (net (code "64") (name "Net-(IC2-VBAT)") (class "Default")
      (node (ref "B3") (pin "2") (pinfunction "2_2") (pintype "passive"))
      (node (ref "IC2") (pin "4") (pinfunction "VBAT_4") (pintype "bidirectional"))
      (node (ref "LED1") (pin "A") (pinfunction "A_A") (pintype "passive"))
      (node (ref "R3") (pin "1") (pinfunction "1_1") (pintype "passive"))
      (node (ref "U1") (pin "3") (pinfunction "VSS_3") (pintype "passive"))
    )
    (net (code "65") (name "Net-(IC3-ADJ)") (class "Default")
      (node (ref "C55") (pin "+") (pinfunction "+_+") (pintype "passive"))
      (node (ref "IC3") (pin "1") (pinfunction "ADJ_1") (pintype "input"))
      (node (ref "R53") (pin "2") (pinfunction "2_2") (pintype "passive"))
      (node (ref "R54") (pin "1") (pinfunction "1_1") (pintype "passive"))
    )
    (net (code "66") (name "Net-(IC3-IN)") (class "Default")
      (node (ref "C53") (pin "+") (pinfunction "+_+") (pintype "passive"))
      (node (ref "C56") (pin "+") (pinfunction "+_+") (pintype "passive"))
      (node (ref "IC3") (pin "2") (pinfunction "IN_2") (pintype "input"))
      (node (ref "IC5") (pin "2") (pinfunction "IN_2") (pintype "input"))
      (node (ref "JP3") (pin "2") (pinfunction "2_2") (pintype "passive"))
      (node (ref "R60") (pin "2") (pinfunction "2_2") (pintype "passive"))
    )
    (net (code "67") (name "Net-(IC4-CLOCK16N)") (class "Default")
      (node (ref "IC4") (pin "20") (pinfunction "CLOCK16N_20") (pintype "bidirectional"))
      (node (ref "Q4") (pin "1") (pinfunction "1_1") (pintype "passive"))
    )
    (net (code "68") (name "Net-(IC4-CLOCK16P)") (class "Default")
      (node (ref "IC4") (pin "19") (pinfunction "CLOCK16P_19") (pintype "bidirectional"))
      (node (ref "Q4") (pin "2") (pinfunction "2_2") (pintype "passive"))
    )
    (net (code "69") (name "Net-(IC4-SYSCLK)") (class "Default")
      (node (ref "IC4") (pin "7") (pinfunction "SYSCLK_7") (pintype "output"))
      (node (ref "RF_SYSCLK") (pin "TP") (pinfunction "TP_TP") (pintype "input"))
    )
    (net (code "70") (name "Net-(IC4-VDD_IO)") (class "Default")
      (node (ref "B6") (pin "2") (pinfunction "2_2") (pintype "passive"))
      (node (ref "C24") (pin "2") (pinfunction "2_2") (pintype "passive"))
      (node (ref "IC4") (pin "15") (pinfunction "VDD_IO_15") (pintype "power_in"))
    )
    (net (code "71") (name "Net-(IC5-ADJ)") (class "Default")
      (node (ref "C58") (pin "+") (pinfunction "+_+") (pintype "passive"))
      (node (ref "IC5") (pin "1") (pinfunction "ADJ_1") (pintype "input"))
      (node (ref "R55") (pin "2") (pinfunction "2_2") (pintype "passive"))
      (node (ref "R56") (pin "1") (pinfunction "1_1") (pintype "passive"))
    )
    (net (code "72") (name "Net-(IC6-ADJ)") (class "Default")
      (node (ref "C61") (pin "+") (pinfunction "+_+") (pintype "passive"))
      (node (ref "IC6") (pin "1") (pinfunction "ADJ_1") (pintype "input"))
      (node (ref "R57") (pin "2") (pinfunction "2_2") (pintype "passive"))
      (node (ref "R58") (pin "1") (pinfunction "1_1") (pintype "passive"))
    )
    (net (code "73") (name "Net-(J4-PadD+)") (class "Default")
      (node (ref "J4") (pin "D+") (pinfunction "D+_D+") (pintype "bidirectional"))
      (node (ref "USB_DP") (pin "TP") (pinfunction "TP_TP") (pintype "input"))
    )
    (net (code "74") (name "Net-(J4-PadD-)") (class "Default")
      (node (ref "J4") (pin "D-") (pinfunction "D-_D-") (pintype "bidirectional"))
      (node (ref "USB_DN") (pin "TP") (pinfunction "TP_TP") (pintype "input"))
    )
    (net (code "75") (name "Net-(J4-PadID)") (class "Default")
      (node (ref "J4") (pin "ID") (pinfunction "ID_ID") (pintype "bidirectional"))
      (node (ref "USB_ID") (pin "TP") (pinfunction "TP_TP") (pintype "input"))
    )
    (net (code "76") (name "Net-(L8-Pad4)") (class "Default")
      (node (ref "L8") (pin "4") (pinfunction "4_4") (pintype "passive"))
      (node (ref "R49") (pin "2") (pinfunction "2_2") (pintype "passive"))
      (node (ref "R50") (pin "2") (pinfunction "2_2") (pintype "passive"))
    )
    (net (code "77") (name "Net-(LED2-PadA)") (class "Default")
      (node (ref "LED2") (pin "A") (pinfunction "A_A") (pintype "passive"))
      (node (ref "R10") (pin "1") (pinfunction "1_1") (pintype "passive"))
    )
    (net (code "78") (name "Net-(LED3-PadA)") (class "Default")
      (node (ref "LED3") (pin "A") (pinfunction "A_A") (pintype "passive"))
      (node (ref "R11") (pin "1") (pinfunction "1_1") (pintype "passive"))
    )
    (net (code "79") (name "Net-(LED4-PadA)") (class "Default")
      (node (ref "LED4") (pin "A") (pinfunction "A_A") (pintype "passive"))
      (node (ref "R14") (pin "1") (pinfunction "1_1") (pintype "passive"))
    )
    (net (code "80") (name "Net-(LED5-PadA)") (class "Default")
      (node (ref "LED5") (pin "A") (pinfunction "A_A") (pintype "passive"))
      (node (ref "R15") (pin "1") (pinfunction "1_1") (pintype "passive"))
    )
    (net (code "81") (name "Net-(LED6-PadA)") (class "Default")
      (node (ref "LED6") (pin "A") (pinfunction "A_A") (pintype "passive"))
      (node (ref "R18") (pin "2") (pinfunction "2_2") (pintype "passive"))
    )
    (net (code "82") (name "Net-(LED7-PadA)") (class "Default")
      (node (ref "LED7") (pin "A") (pinfunction "A_A") (pintype "passive"))
      (node (ref "R19") (pin "2") (pinfunction "2_2") (pintype "passive"))
    )
    (net (code "83") (name "Net-(LED8-PadA)") (class "Default")
      (node (ref "LED8") (pin "A") (pinfunction "A_A") (pintype "passive"))
      (node (ref "R20") (pin "2") (pinfunction "2_2") (pintype "passive"))
    )
    (net (code "84") (name "Net-(LED9-PadA)") (class "Default")
      (node (ref "LED9") (pin "A") (pinfunction "A_A") (pintype "passive"))
      (node (ref "R21") (pin "2") (pinfunction "2_2") (pintype "passive"))
    )
    (net (code "85") (name "Net-(LED10-PadA)") (class "Default")
      (node (ref "LED10") (pin "A") (pinfunction "A_A") (pintype "passive"))
      (node (ref "R22") (pin "2") (pinfunction "2_2") (pintype "passive"))
    )
    (net (code "86") (name "Net-(LED11-PadA)") (class "Default")
      (node (ref "LED11") (pin "A") (pinfunction "A_A") (pintype "passive"))
      (node (ref "R23") (pin "2") (pinfunction "2_2") (pintype "passive"))
    )
    (net (code "87") (name "Net-(LED12-PadA)") (class "Default")
      (node (ref "LED12") (pin "A") (pinfunction "A_A") (pintype "passive"))
      (node (ref "R24") (pin "2") (pinfunction "2_2") (pintype "passive"))
    )
    (net (code "88") (name "Net-(Q2-PadB)") (class "Default")
      (node (ref "Q2") (pin "B") (pinfunction "B_B") (pintype "passive"))
      (node (ref "R28") (pin "1") (pinfunction "1_1") (pintype "passive"))
      (node (ref "R29") (pin "2") (pinfunction "2_2") (pintype "passive"))
    )
    (net (code "89") (name "Net-(Q2-PadE)") (class "Default")
      (node (ref "Q2") (pin "E") (pinfunction "E_E") (pintype "passive"))
      (node (ref "R27") (pin "1") (pinfunction "1_1") (pintype "passive"))
    )
    (net (code "90") (name "Net-(Q3-D)") (class "Default")
      (node (ref "D1") (pin "A") (pinfunction "A_A") (pintype "passive"))
      (node (ref "JP2") (pin "2") (pinfunction "2_2") (pintype "passive"))
      (node (ref "Q3") (pin "3") (pinfunction "D_3") (pintype "passive"))
    )
    (net (code "91") (name "Net-(Q5-Pad1)") (class "Default")
      (node (ref "Q5") (pin "1") (pinfunction "1_1") (pintype "passive"))
      (node (ref "Q5") (pin "2") (pinfunction "2_2") (pintype "passive"))
      (node (ref "Q5") (pin "3") (pinfunction "3_3") (pintype "passive"))
      (node (ref "R36") (pin "1") (pinfunction "1_1") (pintype "passive"))
      (node (ref "R38") (pin "2") (pinfunction "2_2") (pintype "passive"))
      (node (ref "R39") (pin "2") (pinfunction "2_2") (pintype "passive"))
    )
    (net (code "92") (name "Net-(Q5-Pad4)") (class "Default")
      (node (ref "Q5") (pin "4") (pinfunction "4_4") (pintype "passive"))
      (node (ref "R39") (pin "1") (pinfunction "1_1") (pintype "passive"))
      (node (ref "R40") (pin "1") (pinfunction "1_1") (pintype "passive"))
    )
    (net (code "93") (name "Net-(Q5-Pad5)") (class "Default")
      (node (ref "Q5") (pin "5") (pinfunction "5_5") (pintype "passive"))
      (node (ref "Q5") (pin "6") (pinfunction "6_6") (pintype "passive"))
      (node (ref "Q5") (pin "7") (pinfunction "7_7") (pintype "passive"))
      (node (ref "Q5") (pin "8") (pinfunction "8_8") (pintype "passive"))
      (node (ref "Q6") (pin "5") (pinfunction "5_5") (pintype "passive"))
      (node (ref "Q6") (pin "6") (pinfunction "6_6") (pintype "passive"))
      (node (ref "Q6") (pin "7") (pinfunction "7_7") (pintype "passive"))
      (node (ref "Q6") (pin "8") (pinfunction "8_8") (pintype "passive"))
    )
    (net (code "94") (name "Net-(Q7-D)") (class "Default")
      (node (ref "Q7") (pin "3") (pinfunction "D_3") (pintype "passive"))
      (node (ref "R46") (pin "1") (pinfunction "1_1") (pintype "passive"))
    )
    (net (code "95") (name "Net-(R46-Pad2)") (class "Default")
      (node (ref "R46") (pin "2") (pinfunction "2_2") (pintype "passive"))
      (node (ref "R47") (pin "2") (pinfunction "2_2") (pintype "passive"))
      (node (ref "R48") (pin "1") (pinfunction "1_1") (pintype "passive"))
    )
    (net (code "96") (name "Net-(U$2-GATE_VOLTAGE)") (class "Default")
      (node (ref "B7") (pin "2") (pinfunction "2_2") (pintype "passive"))
      (node (ref "U$2") (pin "3") (pinfunction "GATE_VOLTAGE_3") (pintype "bidirectional"))
    )
    (net (code "97") (name "Net-(U2-PH0-OSC_IN)") (class "Default")
      (node (ref "C14") (pin "1") (pinfunction "1_1") (pintype "passive"))
      (node (ref "Q1") (pin "2") (pinfunction "2_2") (pintype "passive"))
      (node (ref "U2") (pin "5") (pinfunction "PH0-OSC_IN_5") (pintype "bidirectional"))
    )
    (net (code "98") (name "Net-(U2-PH1-OSC_OUT)") (class "Default")
      (node (ref "R9") (pin "2") (pinfunction "2_2") (pintype "passive"))
      (node (ref "U2") (pin "6") (pinfunction "PH1-OSC_OUT_6") (pintype "bidirectional"))
    )
    (net (code "99") (name "Net-(U3-D+)") (class "Default")
      (node (ref "J1") (pin "D+") (pinfunction "D+_D+") (pintype "bidirectional"))
      (node (ref "U3") (pin "19") (pinfunction "D+_19") (pintype "bidirectional"))
    )
    (net (code "100") (name "Net-(U3-D-)") (class "Default")
      (node (ref "J1") (pin "D-") (pinfunction "D-_D-") (pintype "bidirectional"))
      (node (ref "U3") (pin "18") (pinfunction "D-_18") (pintype "bidirectional"))
    )
    (net (code "101") (name "Net-(U3-GP6{slash}RXLED)") (class "Default")
      (node (ref "LED11") (pin "C") (pinfunction "C_C") (pintype "passive"))
      (node (ref "U3") (pin "6") (pinfunction "GP6/RXLED_6") (pintype "bidirectional"))
    )
    (net (code "102") (name "Net-(U3-GP7{slash}TXLED)") (class "Default")
      (node (ref "LED12") (pin "C") (pinfunction "C_C") (pintype "passive"))
      (node (ref "U3") (pin "5") (pinfunction "GP7/TXLED_5") (pintype "bidirectional"))
    )
    (net (code "103") (name "Net-(U3-VDD)") (class "Default")
      (node (ref "J1") (pin "VBUS") (pinfunction "VBUS_VBUS") (pintype "power_in"))
      (node (ref "U3") (pin "1") (pinfunction "VDD_1") (pintype "power_in"))
    )
    (net (code "104") (name "Net-(U3-VUSB)") (class "Default")
      (node (ref "C20") (pin "1") (pinfunction "1_1") (pintype "passive"))
      (node (ref "U3") (pin "17") (pinfunction "VUSB_17") (pintype "power_in"))
    )
    (net (code "105") (name "Net-(U4-IO3)") (class "Default")
      (node (ref "J2") (pin "ID") (pinfunction "ID_ID") (pintype "bidirectional"))
      (node (ref "R26") (pin "1") (pinfunction "1_1") (pintype "passive"))
      (node (ref "U4") (pin "4") (pinfunction "IO3_4") (pintype "bidirectional"))
    )
    (net (code "106") (name "Net-(U4-VCC)") (class "Default")
      (node (ref "FB1") (pin "2") (pinfunction "2_2") (pintype "passive"))
      (node (ref "R29") (pin "1") (pinfunction "1_1") (pintype "passive"))
      (node (ref "U4") (pin "5") (pinfunction "VCC_5") (pintype "power_in"))
    )
    (net (code "107") (name "Net-(U5-AVDD)") (class "Default")
      (node (ref "C42") (pin "2") (pinfunction "2_2") (pintype "passive"))
      (node (ref "U5") (pin "17") (pinfunction "CCFG_17") (pintype "bidirectional"))
      (node (ref "U5") (pin "2") (pinfunction "AVDD_2") (pintype "bidirectional"))
    )
    (net (code "108") (name "Net-(U5-AVSS)") (class "Default")
      (node (ref "BAT") (pin "5") (pinfunction "5_5") (pintype "passive"))
      (node (ref "C38") (pin "2") (pinfunction "2_2") (pintype "passive"))
      (node (ref "C39") (pin "2") (pinfunction "2_2") (pintype "passive"))
      (node (ref "C40") (pin "2") (pinfunction "2_2") (pintype "passive"))
      (node (ref "C41") (pin "2") (pinfunction "2_2") (pintype "passive"))
      (node (ref "C42") (pin "1") (pinfunction "1_1") (pintype "passive"))
      (node (ref "C43") (pin "2") (pinfunction "2_2") (pintype "passive"))
      (node (ref "C44") (pin "1") (pinfunction "1_1") (pintype "passive"))
      (node (ref "C46") (pin "2") (pinfunction "2_2") (pintype "passive"))
      (node (ref "R36") (pin "2") (pinfunction "2_2") (pintype "passive"))
      (node (ref "R37") (pin "2") (pinfunction "2_2") (pintype "passive"))
      (node (ref "R62") (pin "2") (pinfunction "2_2") (pintype "passive"))
      (node (ref "U5") (pin "18") (pinfunction "CTRC_18") (pintype "bidirectional"))
      (node (ref "U5") (pin "19") (pinfunction "CTRD_19") (pintype "bidirectional"))
      (node (ref "U5") (pin "20") (pinfunction "DVSS_20") (pintype "bidirectional"))
      (node (ref "U5") (pin "8") (pinfunction "AVSS_8") (pintype "bidirectional"))
    )
    (net (code "109") (name "Net-(U5-CHG)") (class "Default")
      (node (ref "R43") (pin "1") (pinfunction "1_1") (pintype "passive"))
      (node (ref "U5") (pin "13") (pinfunction "CHG_13") (pintype "bidirectional"))
    )
    (net (code "110") (name "Net-(U5-DSG)") (class "Default")
      (node (ref "R40") (pin "2") (pinfunction "2_2") (pintype "passive"))
      (node (ref "U5") (pin "11") (pinfunction "DSG_11") (pintype "bidirectional"))
    )
    (net (code "111") (name "Net-(U5-LD)") (class "Default")
      (node (ref "R44") (pin "1") (pinfunction "1_1") (pintype "passive"))
      (node (ref "U5") (pin "14") (pinfunction "LD_14") (pintype "bidirectional"))
    )
    (net (code "112") (name "Net-(U5-SRN)") (class "Default")
      (node (ref "C45") (pin "2") (pinfunction "2_2") (pintype "passive"))
      (node (ref "C46") (pin "1") (pinfunction "1_1") (pintype "passive"))
      (node (ref "R38") (pin "1") (pinfunction "1_1") (pintype "passive"))
      (node (ref "U5") (pin "10") (pinfunction "SRN_10") (pintype "bidirectional"))
    )
    (net (code "113") (name "Net-(U5-SRP)") (class "Default")
      (node (ref "C44") (pin "2") (pinfunction "2_2") (pintype "passive"))
      (node (ref "C45") (pin "1") (pinfunction "1_1") (pintype "passive"))
      (node (ref "R37") (pin "1") (pinfunction "1_1") (pintype "passive"))
      (node (ref "U5") (pin "9") (pinfunction "SRP_9") (pintype "bidirectional"))
    )
    (net (code "114") (name "Net-(U5-TS)") (class "Default")
      (node (ref "R35") (pin "2") (pinfunction "2_2") (pintype "passive"))
      (node (ref "R62") (pin "1") (pinfunction "1_1") (pintype "passive"))
      (node (ref "U5") (pin "15") (pinfunction "TS_15") (pintype "bidirectional"))
    )
    (net (code "115") (name "Net-(U5-VC1)") (class "Default")
      (node (ref "C39") (pin "1") (pinfunction "1_1") (pintype "passive"))
      (node (ref "R33") (pin "2") (pinfunction "2_2") (pintype "passive"))
      (node (ref "U5") (pin "7") (pinfunction "VC1_7") (pintype "bidirectional"))
    )
    (net (code "116") (name "Net-(U5-VC2)") (class "Default")
      (node (ref "C40") (pin "1") (pinfunction "1_1") (pintype "passive"))
      (node (ref "R32") (pin "2") (pinfunction "2_2") (pintype "passive"))
      (node (ref "U5") (pin "6") (pinfunction "VC2_6") (pintype "bidirectional"))
    )
    (net (code "117") (name "Net-(U5-VC3)") (class "Default")
      (node (ref "C41") (pin "1") (pinfunction "1_1") (pintype "passive"))
      (node (ref "R31") (pin "2") (pinfunction "2_2") (pintype "passive"))
      (node (ref "U5") (pin "5") (pinfunction "VC3_5") (pintype "bidirectional"))
    )
    (net (code "118") (name "Net-(U5-VC4)") (class "Default")
      (node (ref "C38") (pin "1") (pinfunction "1_1") (pintype "passive"))
      (node (ref "R30") (pin "2") (pinfunction "2_2") (pintype "passive"))
      (node (ref "U5") (pin "3") (pinfunction "VC5_3") (pintype "bidirectional"))
      (node (ref "U5") (pin "4") (pinfunction "VC4_4") (pintype "bidirectional"))
    )
    (net (code "119") (name "Net-(U5-VDD)") (class "Default")
      (node (ref "C43") (pin "1") (pinfunction "1_1") (pintype "passive"))
      (node (ref "R34") (pin "2") (pinfunction "2_2") (pintype "passive"))
      (node (ref "U5") (pin "1") (pinfunction "VDD_1") (pintype "bidirectional"))
    )
    (net (code "120") (name "Net-(U5-VTB)") (class "Default")
      (node (ref "R35") (pin "1") (pinfunction "1_1") (pintype "passive"))
      (node (ref "U5") (pin "16") (pinfunction "VTB_16") (pintype "bidirectional"))
    )
    (net (code "121") (name "POW_LED_G1") (class "Default")
      (node (ref "R20") (pin "1") (pinfunction "1_1") (pintype "passive"))
      (node (ref "U2") (pin "22") (pinfunction "PA6_22") (pintype "bidirectional"))
    )
    (net (code "122") (name "POW_LED_G2") (class "Default")
      (node (ref "R19") (pin "1") (pinfunction "1_1") (pintype "passive"))
      (node (ref "U2") (pin "21") (pinfunction "PA5_21") (pintype "bidirectional"))
    )
    (net (code "123") (name "POW_LED_G3") (class "Default")
      (node (ref "R18") (pin "1") (pinfunction "1_1") (pintype "passive"))
      (node (ref "U2") (pin "20") (pinfunction "PA4_20") (pintype "bidirectional"))
    )
    (net (code "124") (name "POW_LED_R") (class "Default")
      (node (ref "R21") (pin "1") (pinfunction "1_1") (pintype "passive"))
      (node (ref "U2") (pin "24") (pinfunction "PC4_24") (pintype "bidirectional"))
    )
    (net (code "125") (name "POW_LED_Y") (class "Default")
      (node (ref "R22") (pin "1") (pinfunction "1_1") (pintype "passive"))
      (node (ref "U2") (pin "23") (pinfunction "PA7_23") (pintype "bidirectional"))
    )
    (net (code "126") (name "RESERVED") (class "Default")
      (node (ref "U2") (pin "30") (pinfunction "PB11_30") (pintype "bidirectional"))
    )
    (net (code "127") (name "RF_SIGNAL") (class "Default")
      (node (ref "C37") (pin "2") (pinfunction "2_2") (pintype "passive"))
      (node (ref "L7") (pin "2") (pinfunction "2_2") (pintype "passive"))
      (node (ref "RF_SIGNAL") (pin "TP") (pinfunction "TP_TP") (pintype "input"))
      (node (ref "U$2") (pin "1") (pinfunction "RF_IN_1") (pintype "bidirectional"))
    )
    (net (code "128") (name "RF_SIGNAL_AMPLIFIED") (class "Default")
      (node (ref "J3") (pin "S") (pinfunction "OUT_S") (pintype "bidirectional"))
      (node (ref "U$2") (pin "4") (pinfunction "RF_OUT_4") (pintype "bidirectional"))
    )
    (net (code "129") (name "SPI2_CLK") (class "Default")
      (node (ref "IC4") (pin "9") (pinfunction "CLK_9") (pintype "input"))
      (node (ref "SPI2_CLK") (pin "TP") (pinfunction "TP_TP") (pintype "input"))
      (node (ref "U2") (pin "29") (pinfunction "PB10_29") (pintype "bidirectional"))
    )
    (net (code "130") (name "SPI2_IRQ") (class "Default")
      (node (ref "IC4") (pin "14") (pinfunction "IRQ_14") (pintype "output"))
      (node (ref "SPI2_IRQ") (pin "TP") (pinfunction "TP_TP") (pintype "input"))
      (node (ref "U2") (pin "8") (pinfunction "PC0_8") (pintype "bidirectional"))
    )
    (net (code "131") (name "SPI2_MISO") (class "Default")
      (node (ref "IC4") (pin "10") (pinfunction "MISO_SDO_10") (pintype "output"))
      (node (ref "SPI2_MISO") (pin "TP") (pinfunction "TP_TP") (pintype "input"))
      (node (ref "U2") (pin "10") (pinfunction "PC2_10") (pintype "bidirectional"))
    )
    (net (code "132") (name "SPI2_MOSI") (class "Default")
      (node (ref "IC4") (pin "12") (pinfunction "MOSI_SDI_12") (pintype "input"))
      (node (ref "SPI2_MOSI") (pin "TP") (pinfunction "TP_TP") (pintype "input"))
      (node (ref "U2") (pin "11") (pinfunction "PC3_11") (pintype "bidirectional"))
    )
    (net (code "133") (name "SPI2_SEL_RFTX") (class "Default")
      (node (ref "IC4") (pin "8") (pinfunction "SEL_8") (pintype "input"))
      (node (ref "SPI2_SEL_RFTX") (pin "TP") (pinfunction "TP_TP") (pintype "input"))
      (node (ref "U2") (pin "9") (pinfunction "PC1_9") (pintype "bidirectional"))
    )
    (net (code "134") (name "SWDCLK") (class "Default")
      (node (ref "PR0>") (pin "3") (pinfunction "3_3") (pintype "passive"))
      (node (ref "U2") (pin "49") (pinfunction "PA14_49") (pintype "bidirectional"))
    )
    (net (code "135") (name "SWDIO") (class "Default")
      (node (ref "PR0>") (pin "2") (pinfunction "2_2") (pintype "passive"))
      (node (ref "U2") (pin "46") (pinfunction "PA13_46") (pintype "bidirectional"))
    )
    (net (code "136") (name "SWD_RX") (class "Default")
      (node (ref "U3") (pin "12") (pinfunction "RX_12") (pintype "input"))
    )
    (net (code "137") (name "SWD_RXD") (class "Default")
      (node (ref "SWD_RXD") (pin "TP") (pinfunction "TP_TP") (pintype "input"))
      (node (ref "U2") (pin "16") (pinfunction "PA2_16") (pintype "bidirectional"))
    )
    (net (code "138") (name "SWD_TX") (class "Default")
      (node (ref "U3") (pin "10") (pinfunction "TX_10") (pintype "output"))
    )
    (net (code "139") (name "SWD_TXD") (class "Default")
      (node (ref "SWD_TXD") (pin "TP") (pinfunction "TP_TP") (pintype "input"))
      (node (ref "U2") (pin "17") (pinfunction "PA3_17") (pintype "bidirectional"))
    )
    (net (code "140") (name "USB_DATA_N") (class "Default")
      (node (ref "J2") (pin "D-") (pinfunction "D-_D-") (pintype "bidirectional"))
      (node (ref "U2") (pin "44") (pinfunction "PA11_44") (pintype "bidirectional"))
      (node (ref "U4") (pin "1") (pinfunction "IO1_1") (pintype "bidirectional"))
    )
    (net (code "141") (name "USB_DATA_P") (class "Default")
      (node (ref "J2") (pin "D+") (pinfunction "D+_D+") (pintype "bidirectional"))
      (node (ref "R27") (pin "2") (pinfunction "2_2") (pintype "passive"))
      (node (ref "U2") (pin "45") (pinfunction "PA12_45") (pintype "bidirectional"))
      (node (ref "U4") (pin "2") (pinfunction "IO2_2") (pintype "bidirectional"))
    )
    (net (code "142") (name "V+STM") (class "Default")
      (node (ref "B1") (pin "2") (pinfunction "2_2") (pintype "passive"))
      (node (ref "C10") (pin "2") (pinfunction "2_2") (pintype "passive"))
      (node (ref "C16") (pin "2") (pinfunction "2_2") (pintype "passive"))
      (node (ref "C4") (pin "1") (pinfunction "1_1") (pintype "passive"))
      (node (ref "C5") (pin "2") (pinfunction "2_2") (pintype "passive"))
      (node (ref "C6") (pin "2") (pinfunction "2_2") (pintype "passive"))
      (node (ref "C8") (pin "1") (pinfunction "1_1") (pintype "passive"))
      (node (ref "C9") (pin "1") (pinfunction "1_1") (pintype "passive"))
      (node (ref "U2") (pin "1") (pinfunction "VLCD_1") (pintype "power_in"))
      (node (ref "U2") (pin "13") (pinfunction "VDDA_13") (pintype "power_in"))
      (node (ref "U2") (pin "19") (pinfunction "VDD_2_19") (pintype "power_in"))
      (node (ref "U2") (pin "32") (pinfunction "VDD_3_32") (pintype "power_in"))
      (node (ref "U2") (pin "64") (pinfunction "VDD_64") (pintype "power_in"))
    )
    (net (code "143") (name "VIBRATOR") (class "Default")
      (node (ref "Q3") (pin "1") (pinfunction "G_1") (pintype "passive"))
      (node (ref "R25") (pin "1") (pinfunction "1_1") (pintype "passive"))
      (node (ref "U2") (pin "50") (pinfunction "PA15_50") (pintype "bidirectional"))
    )
    (net (code "144") (name "unconnected-(D8-PadA)") (class "Default")
      (node (ref "D8") (pin "A") (pinfunction "A_A") (pintype "passive"))
    )
    (net (code "145") (name "unconnected-(D9-PadA)") (class "Default")
      (node (ref "D9") (pin "A") (pinfunction "A_A") (pintype "passive"))
    )
    (net (code "146") (name "unconnected-(IC2-BK_O-Pad10)") (class "Default")
      (node (ref "IC2") (pin "10") (pinfunction "BK_O_10") (pintype "bidirectional"))
    )
    (net (code "147") (name "unconnected-(IC2-NC-Pad20)") (class "Default")
      (node (ref "IC2") (pin "20") (pinfunction "NC_20") (pintype "no_connect"))
    )
    (net (code "148") (name "unconnected-(IC2-P0_0{slash}CTS-Pad15)") (class "Default")
      (node (ref "IC2") (pin "15") (pinfunction "P0_0/CTS_15") (pintype "bidirectional"))
    )
    (net (code "149") (name "unconnected-(IC2-P0_7-Pad29)") (class "Default")
      (node (ref "IC2") (pin "29") (pinfunction "P0_7_29") (pintype "bidirectional"))
    )
    (net (code "150") (name "unconnected-(IC2-P1_0-Pad16)") (class "Default")
      (node (ref "IC2") (pin "16") (pinfunction "P1_0_16") (pintype "bidirectional"))
    )
    (net (code "151") (name "unconnected-(IC2-P1_1-Pad12)") (class "Default")
      (node (ref "IC2") (pin "12") (pinfunction "P1_1_12") (pintype "bidirectional"))
    )
    (net (code "152") (name "unconnected-(IC2-P1_2{slash}SCL-Pad13)") (class "Default")
      (node (ref "IC2") (pin "13") (pinfunction "P1_2/SCL_13") (pintype "bidirectional"))
    )
    (net (code "153") (name "unconnected-(IC2-P1_3{slash}SDA-Pad14)") (class "Default")
      (node (ref "IC2") (pin "14") (pinfunction "P1_3/SDA_14") (pintype "bidirectional"))
    )
    (net (code "154") (name "unconnected-(IC2-P2_2-Pad5)") (class "Default")
      (node (ref "IC2") (pin "5") (pinfunction "P2_2_5") (pintype "bidirectional"))
    )
    (net (code "155") (name "unconnected-(IC2-P2_3-Pad9)") (class "Default")
      (node (ref "IC2") (pin "9") (pinfunction "P2_3_9") (pintype "bidirectional"))
    )
    (net (code "156") (name "unconnected-(IC2-P2_4-Pad19)") (class "Default")
      (node (ref "IC2") (pin "19") (pinfunction "P2_4_19") (pintype "bidirectional"))
    )
    (net (code "157") (name "unconnected-(IC2-P2_7{slash}TX_IND-Pad11)") (class "Default")
      (node (ref "IC2") (pin "11") (pinfunction "P2_7/TX_IND_11") (pintype "bidirectional"))
    )
    (net (code "158") (name "unconnected-(IC2-P3_1-Pad24)") (class "Default")
      (node (ref "IC2") (pin "24") (pinfunction "P3_1_24") (pintype "bidirectional"))
    )
    (net (code "159") (name "unconnected-(IC2-P3_2-Pad25)") (class "Default")
      (node (ref "IC2") (pin "25") (pinfunction "P3_2_25") (pintype "bidirectional"))
    )
    (net (code "160") (name "unconnected-(IC2-P3_3-Pad26)") (class "Default")
      (node (ref "IC2") (pin "26") (pinfunction "P3_3_26") (pintype "bidirectional"))
    )
    (net (code "161") (name "unconnected-(IC2-P3_4-Pad27)") (class "Default")
      (node (ref "IC2") (pin "27") (pinfunction "P3_4_27") (pintype "bidirectional"))
    )
    (net (code "162") (name "unconnected-(IC2-P3_5-Pad28)") (class "Default")
      (node (ref "IC2") (pin "28") (pinfunction "P3_5_28") (pintype "bidirectional"))
    )
    (net (code "163") (name "unconnected-(IC2-P3_6{slash}RTS-Pad17)") (class "Default")
      (node (ref "IC2") (pin "17") (pinfunction "P3_6/RTS_17") (pintype "bidirectional"))
    )
    (net (code "164") (name "unconnected-(IC2-ULC_O-Pad8)") (class "Default")
      (node (ref "IC2") (pin "8") (pinfunction "ULC_O_8") (pintype "bidirectional"))
    )
    (net (code "165") (name "unconnected-(IC2-VDD_IO(1)-Pad6)") (class "Default")
      (node (ref "IC2") (pin "6") (pinfunction "VDD_IO(1)_6") (pintype "bidirectional"))
    )
    (net (code "166") (name "unconnected-(IC2-VDD_IO(2)-Pad7)") (class "Default")
      (node (ref "IC2") (pin "7") (pinfunction "VDD_IO(2)_7") (pintype "bidirectional"))
    )
    (net (code "167") (name "unconnected-(IC4-NC1-Pad5)") (class "Default")
      (node (ref "IC4") (pin "5") (pinfunction "NC1_5") (pintype "no_connect"))
    )
    (net (code "168") (name "unconnected-(IC4-NC2-Pad6)") (class "Default")
      (node (ref "IC4") (pin "6") (pinfunction "NC2_6") (pintype "no_connect"))
    )
    (net (code "169") (name "unconnected-(IC4-NC3-Pad11)") (class "Default")
      (node (ref "IC4") (pin "11") (pinfunction "NC3_11") (pintype "no_connect"))
    )
    (net (code "170") (name "unconnected-(IC4-NC4-Pad13)") (class "Default")
      (node (ref "IC4") (pin "13") (pinfunction "NC4_13") (pintype "no_connect"))
    )
    (net (code "171") (name "unconnected-(IC4-NC5-Pad16)") (class "Default")
      (node (ref "IC4") (pin "16") (pinfunction "NC5_16") (pintype "no_connect"))
    )
    (net (code "172") (name "unconnected-(IC4-NC6-Pad18)") (class "Default")
      (node (ref "IC4") (pin "18") (pinfunction "NC6_18") (pintype "no_connect"))
    )
    (net (code "173") (name "unconnected-(J1-PadID)") (class "Default")
      (node (ref "J1") (pin "ID") (pinfunction "ID_ID") (pintype "bidirectional"))
    )
    (net (code "174") (name "unconnected-(U2-PB3-Pad55)") (class "Default")
      (node (ref "U2") (pin "55") (pinfunction "PB3_55") (pintype "bidirectional"))
    )
    (net (code "175") (name "unconnected-(U2-PB4-Pad56)") (class "Default")
      (node (ref "U2") (pin "56") (pinfunction "PB4_56") (pintype "bidirectional"))
    )
    (net (code "176") (name "unconnected-(U2-PB5-Pad57)") (class "Default")
      (node (ref "U2") (pin "57") (pinfunction "PB5_57") (pintype "bidirectional"))
    )
    (net (code "177") (name "unconnected-(U2-PB6-Pad58)") (class "Default")
      (node (ref "U2") (pin "58") (pinfunction "PB6_58") (pintype "bidirectional"))
    )
    (net (code "178") (name "unconnected-(U2-PB7-Pad59)") (class "Default")
      (node (ref "U2") (pin "59") (pinfunction "PB7_59") (pintype "bidirectional"))
    )
    (net (code "179") (name "unconnected-(U2-PB8-Pad61)") (class "Default")
      (node (ref "U2") (pin "61") (pinfunction "PB8_61") (pintype "bidirectional"))
    )
    (net (code "180") (name "unconnected-(U2-PB9-Pad62)") (class "Default")
      (node (ref "U2") (pin "62") (pinfunction "PB9_62") (pintype "bidirectional"))
    )
    (net (code "181") (name "unconnected-(U2-PC13-Pad2)") (class "Default")
      (node (ref "U2") (pin "2") (pinfunction "PC13_2") (pintype "bidirectional"))
    )
    (net (code "182") (name "unconnected-(U2-PC14-OSC32_IN-Pad3)") (class "Default")
      (node (ref "U2") (pin "3") (pinfunction "PC14-OSC32_IN_3") (pintype "bidirectional"))
    )
    (net (code "183") (name "unconnected-(U2-PC15-OSC32_OUT-Pad4)") (class "Default")
      (node (ref "U2") (pin "4") (pinfunction "PC15-OSC32_OUT_4") (pintype "bidirectional"))
    )
    (net (code "184") (name "unconnected-(U3-GP0{slash}SSPND-Pad16)") (class "Default")
      (node (ref "U3") (pin "16") (pinfunction "GP0/SSPND_16") (pintype "bidirectional"))
    )
    (net (code "185") (name "unconnected-(U3-GP1{slash}USBCFG-Pad15)") (class "Default")
      (node (ref "U3") (pin "15") (pinfunction "GP1/USBCFG_15") (pintype "bidirectional"))
    )
    (net (code "186") (name "unconnected-(U3-GP2-Pad14)") (class "Default")
      (node (ref "U3") (pin "14") (pinfunction "GP2_14") (pintype "bidirectional"))
    )
    (net (code "187") (name "unconnected-(U3-GP3-Pad9)") (class "Default")
      (node (ref "U3") (pin "9") (pinfunction "GP3_9") (pintype "bidirectional"))
    )
    (net (code "188") (name "unconnected-(U3-GP4-Pad8)") (class "Default")
      (node (ref "U3") (pin "8") (pinfunction "GP4_8") (pintype "bidirectional"))
    )
    (net (code "189") (name "unconnected-(U3-GP5-Pad7)") (class "Default")
      (node (ref "U3") (pin "7") (pinfunction "GP5_7") (pintype "bidirectional"))
    )
    (net (code "190") (name "unconnected-(U3-N_CTS-Pad13)") (class "Default")
      (node (ref "U3") (pin "13") (pinfunction "N_CTS_13") (pintype "input"))
    )
    (net (code "191") (name "unconnected-(U3-N_RTS-Pad11)") (class "Default")
      (node (ref "U3") (pin "11") (pinfunction "N_RTS_11") (pintype "output"))
    )
    (net (code "192") (name "unconnected-(U5-CHGU-Pad12)") (class "Default")
      (node (ref "U5") (pin "12") (pinfunction "CHGU_12") (pintype "bidirectional"))
    )
  )
)
